# testhat1.net
KiCad netlist of a schematic drawn in Altium Designer
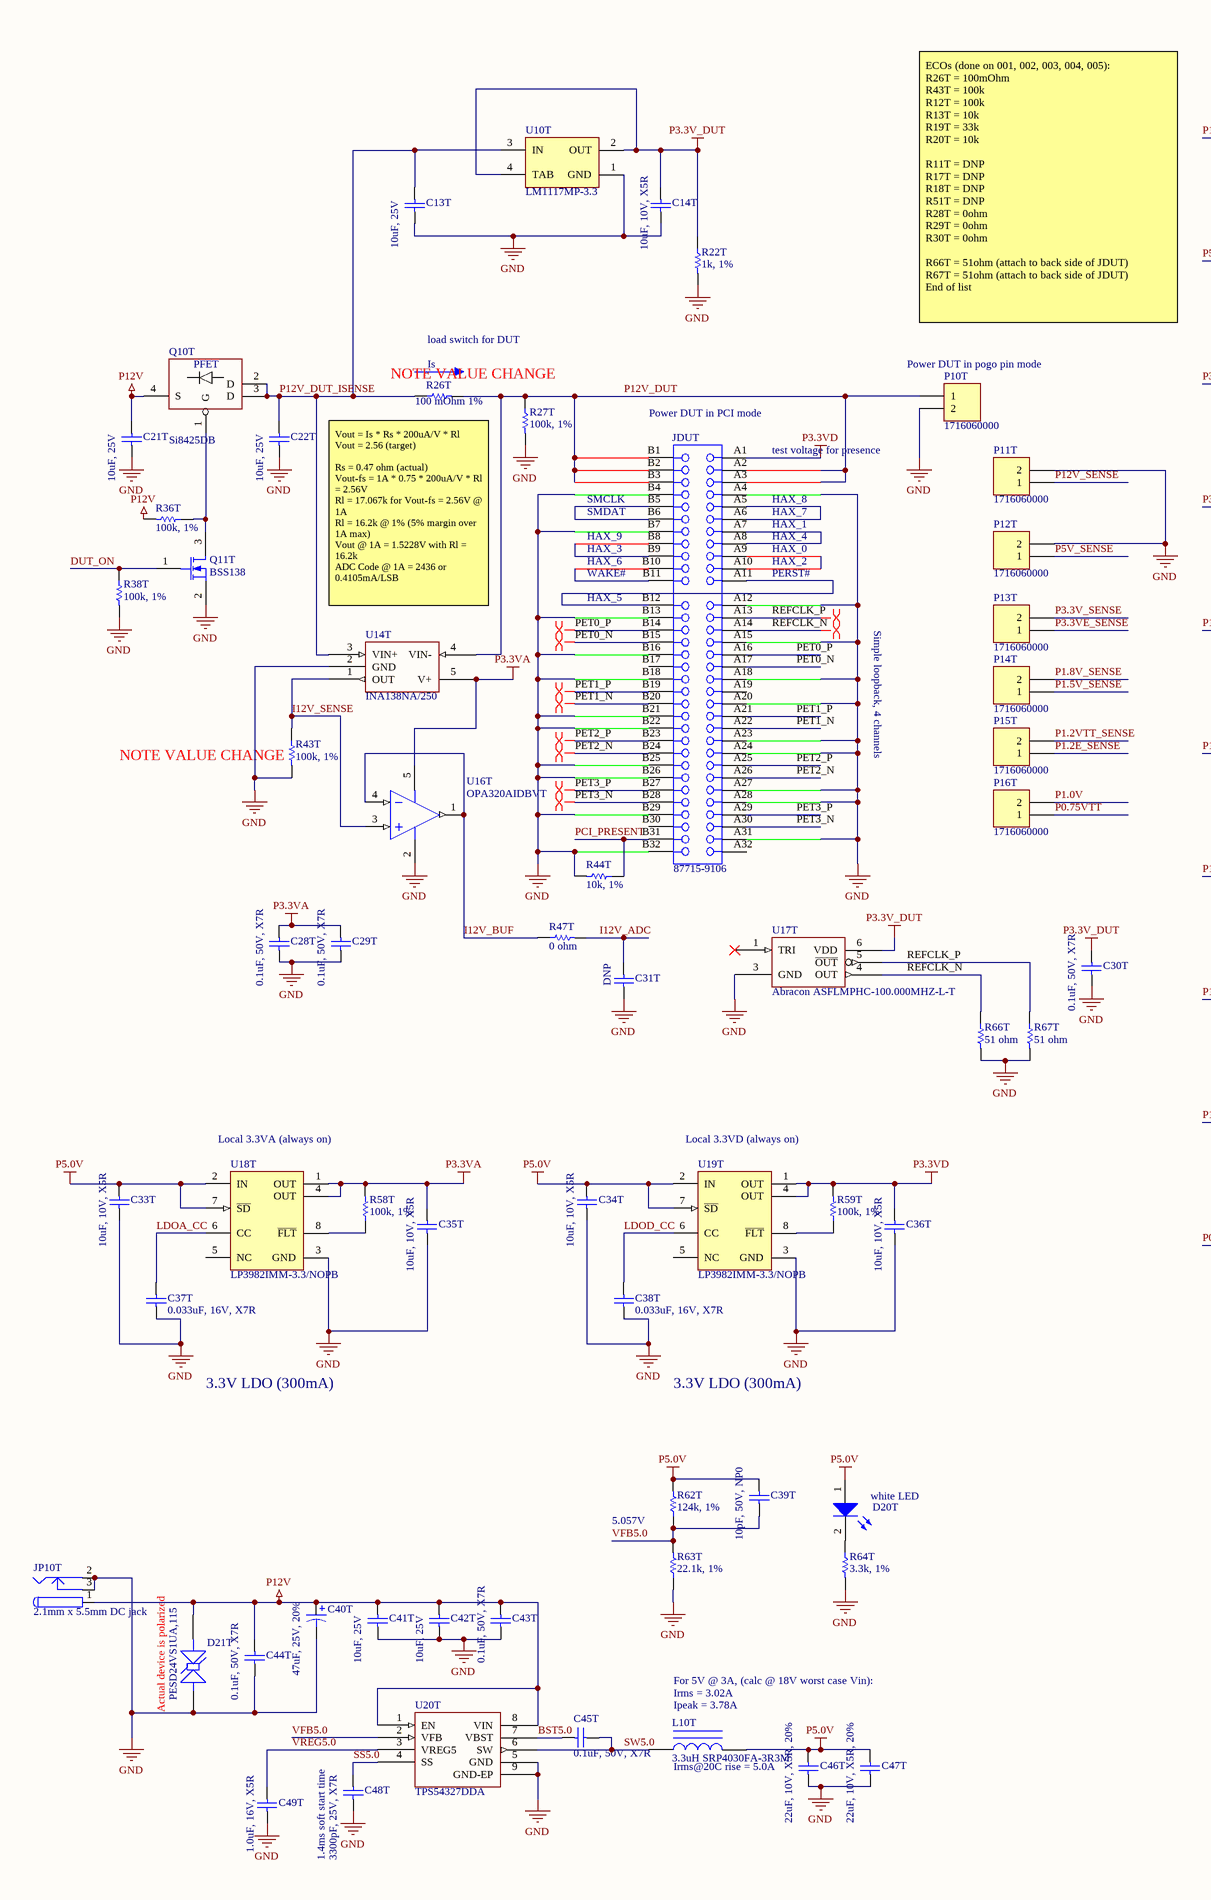
[diagram p0: testhat1.SchDoc, left]
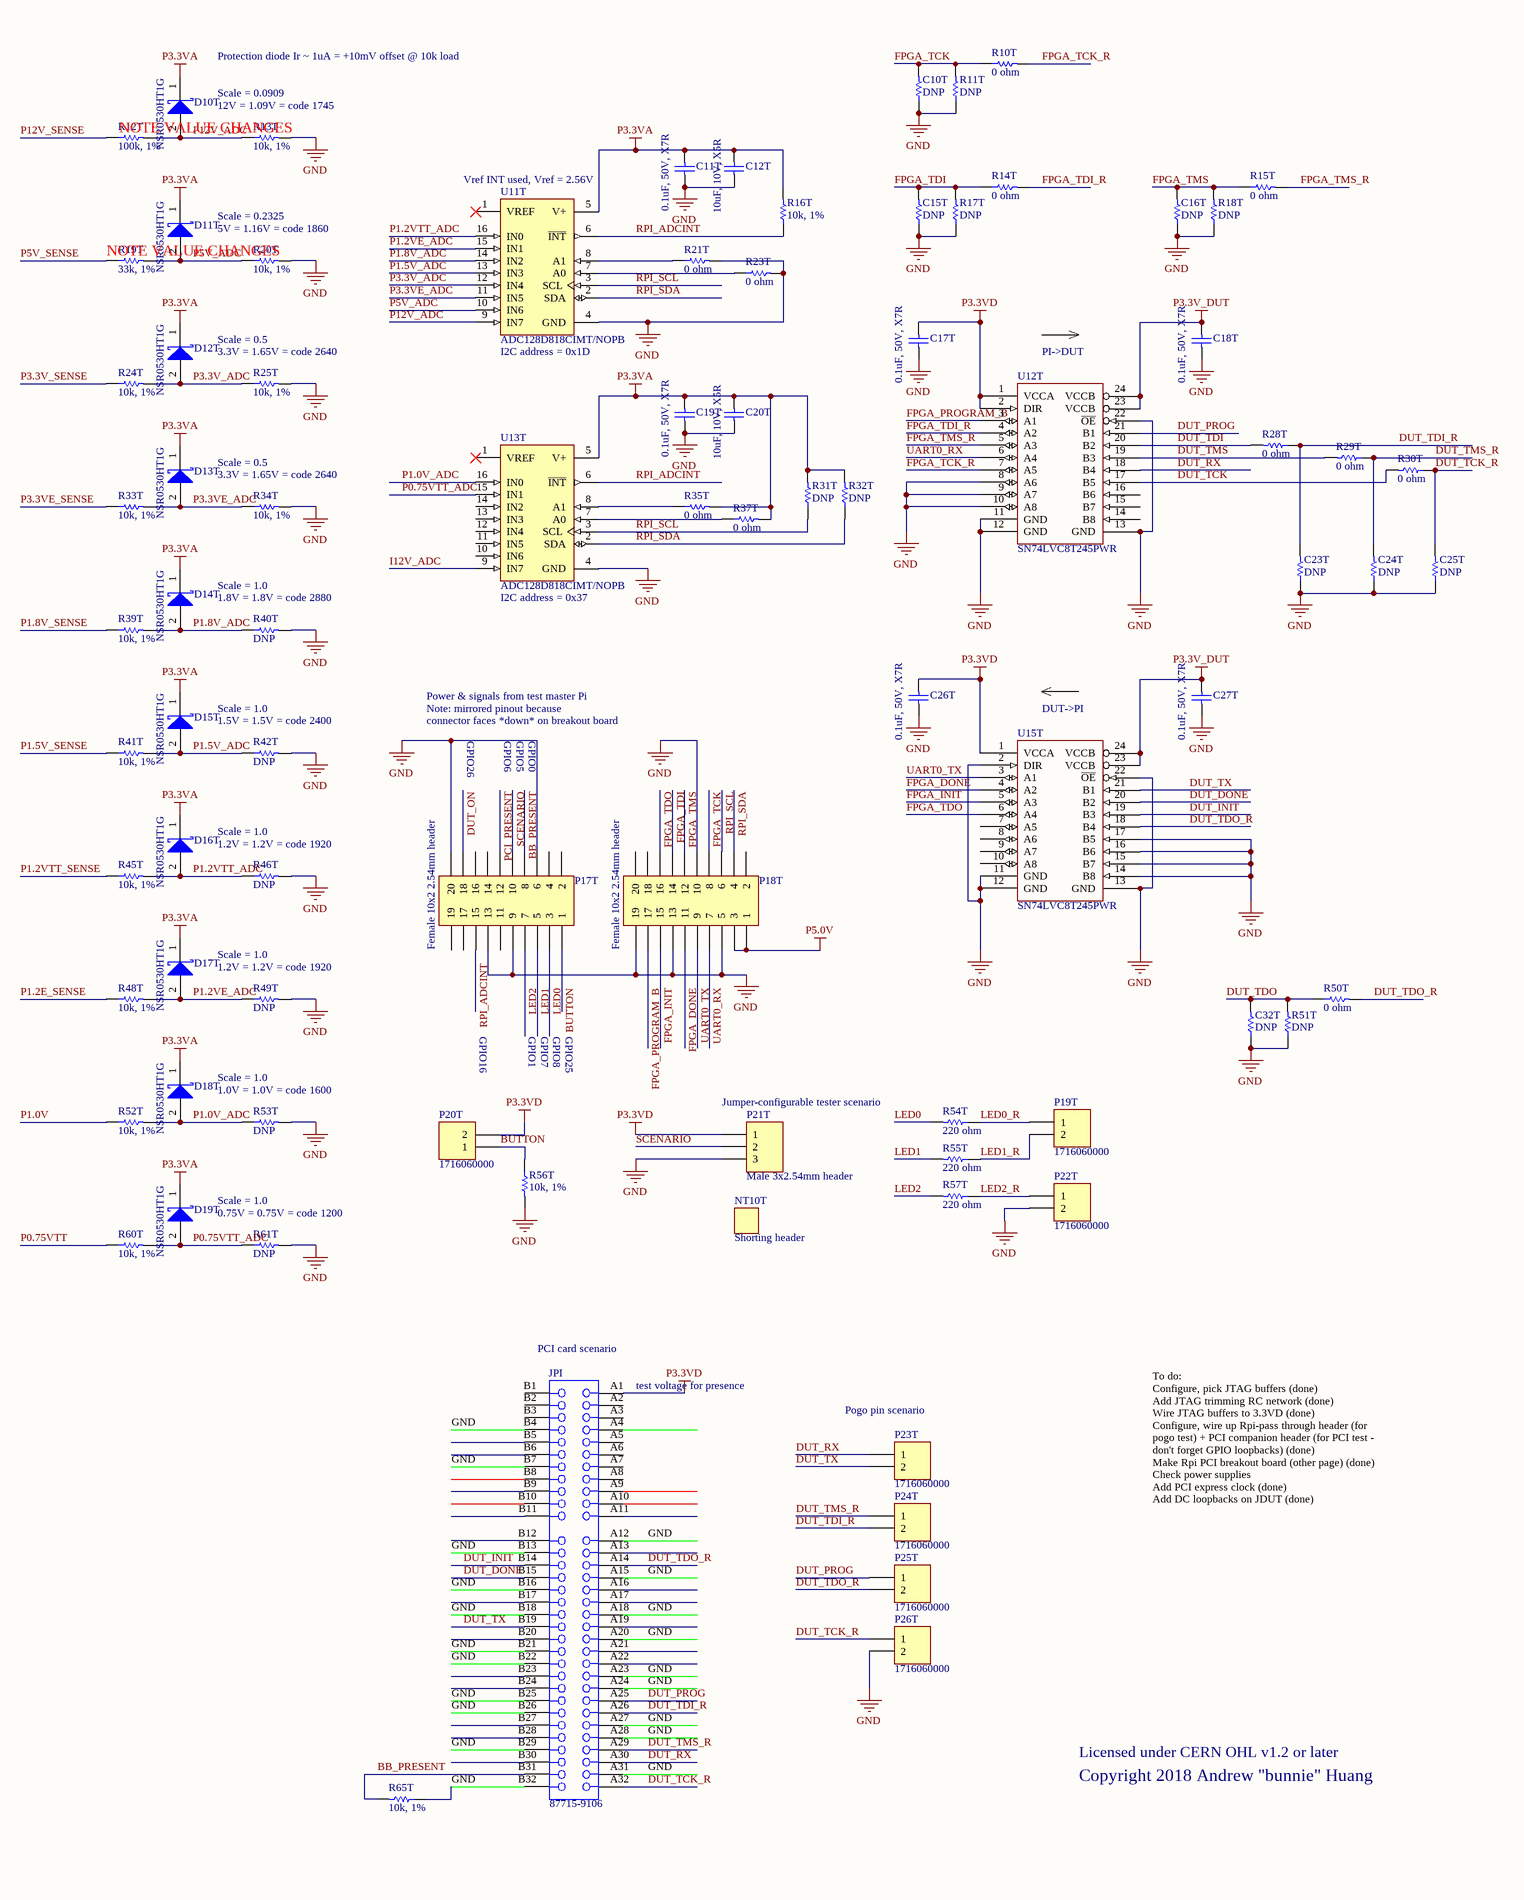
[diagram p1: testhat1.SchDoc, right]

(export (version "E")
  (design (tool "Eeschema 10.0.6"))
  (components
    (comp (ref "C10T")
      (value "DNP")
      (footprint "RESC1608N")
      (description "Resistor")
      (fields (field (name "MPN") "ANY"))
      (libsource (lib "Miscellaneous Devices") (part "Res1"))
    )
    (comp (ref "C11T")
      (value "0.1uF, 50V, X7R")
      (footprint "CAPC2012N")
      (description "Capacitor (Semiconductor SIM Model)")
      (fields (field (name "MPN") "CL21B104KBCNNWC"))
      (libsource (lib "Miscellaneous Devices") (part "Cap Semi"))
    )
    (comp (ref "C12T")
      (value "10uF, 10V, X5R")
      (footprint "CAPC2012N")
      (description "Capacitor (Semiconductor SIM Model)")
      (fields (field (name "MPN") "CL21A106KPCLQNC"))
      (libsource (lib "Miscellaneous Devices") (part "Cap Semi"))
    )
    (comp (ref "C13T")
      (value "10uF, 25V")
      (footprint "CAPC3216N")
      (description "Capacitor (Semiconductor SIM Model)")
      (fields (field (name "MPN") "CL31A106KBHNNNE"))
      (libsource (lib "Miscellaneous Devices") (part "Cap Semi"))
    )
    (comp (ref "C14T")
      (value "10uF, 10V, X5R")
      (footprint "CAPC2012N")
      (description "Capacitor (Semiconductor SIM Model)")
      (fields (field (name "MPN") "CL21A106KPCLQNC"))
      (libsource (lib "Miscellaneous Devices") (part "Cap Semi"))
    )
    (comp (ref "C15T")
      (value "DNP")
      (footprint "RESC1608N")
      (description "Resistor")
      (fields (field (name "MPN") "ANY"))
      (libsource (lib "Miscellaneous Devices") (part "Res1"))
    )
    (comp (ref "C16T")
      (value "DNP")
      (footprint "RESC1608N")
      (description "Resistor")
      (fields (field (name "MPN") "ANY"))
      (libsource (lib "Miscellaneous Devices") (part "Res1"))
    )
    (comp (ref "C17T")
      (value "0.1uF, 50V, X7R")
      (footprint "CAPC2012N")
      (description "Capacitor (Semiconductor SIM Model)")
      (fields (field (name "MPN") "CL21B104KBCNNWC"))
      (libsource (lib "Miscellaneous Devices") (part "Cap Semi"))
    )
    (comp (ref "C18T")
      (value "0.1uF, 50V, X7R")
      (footprint "CAPC2012N")
      (description "Capacitor (Semiconductor SIM Model)")
      (fields (field (name "MPN") "CL21B104KBCNNWC"))
      (libsource (lib "Miscellaneous Devices") (part "Cap Semi"))
    )
    (comp (ref "C19T")
      (value "0.1uF, 50V, X7R")
      (footprint "CAPC2012N")
      (description "Capacitor (Semiconductor SIM Model)")
      (fields (field (name "MPN") "CL21B104KBCNNWC"))
      (libsource (lib "Miscellaneous Devices") (part "Cap Semi"))
    )
    (comp (ref "C20T")
      (value "10uF, 10V, X5R")
      (footprint "CAPC2012N")
      (description "Capacitor (Semiconductor SIM Model)")
      (fields (field (name "MPN") "CL21A106KPCLQNC"))
      (libsource (lib "Miscellaneous Devices") (part "Cap Semi"))
    )
    (comp (ref "C21T")
      (value "10uF, 25V")
      (footprint "CAPC3216N")
      (description "Capacitor (Semiconductor SIM Model)")
      (fields (field (name "MPN") "CL31A106KBHNNNE"))
      (libsource (lib "Miscellaneous Devices") (part "Cap Semi"))
    )
    (comp (ref "C22T")
      (value "10uF, 25V")
      (footprint "CAPC3216N")
      (description "Capacitor (Semiconductor SIM Model)")
      (fields (field (name "MPN") "CL31A106KBHNNNE"))
      (libsource (lib "Miscellaneous Devices") (part "Cap Semi"))
    )
    (comp (ref "C23T")
      (value "DNP")
      (footprint "RESC1608N")
      (description "Resistor")
      (fields (field (name "MPN") "ANY"))
      (libsource (lib "Miscellaneous Devices") (part "Res1"))
    )
    (comp (ref "C24T")
      (value "DNP")
      (footprint "RESC1608N")
      (description "Resistor")
      (fields (field (name "MPN") "ANY"))
      (libsource (lib "Miscellaneous Devices") (part "Res1"))
    )
    (comp (ref "C25T")
      (value "DNP")
      (footprint "RESC1608N")
      (description "Resistor")
      (fields (field (name "MPN") "ANY"))
      (libsource (lib "Miscellaneous Devices") (part "Res1"))
    )
    (comp (ref "C26T")
      (value "0.1uF, 50V, X7R")
      (footprint "CAPC2012N")
      (description "Capacitor (Semiconductor SIM Model)")
      (fields (field (name "MPN") "CL21B104KBCNNWC"))
      (libsource (lib "Miscellaneous Devices") (part "Cap Semi"))
    )
    (comp (ref "C27T")
      (value "0.1uF, 50V, X7R")
      (footprint "CAPC2012N")
      (description "Capacitor (Semiconductor SIM Model)")
      (fields (field (name "MPN") "CL21B104KBCNNWC"))
      (libsource (lib "Miscellaneous Devices") (part "Cap Semi"))
    )
    (comp (ref "C28T")
      (value "0.1uF, 50V, X7R")
      (footprint "CAPC2012N")
      (description "Capacitor (Semiconductor SIM Model)")
      (fields (field (name "MPN") "CL21B104KBCNNWC"))
      (libsource (lib "Miscellaneous Devices") (part "Cap Semi"))
    )
    (comp (ref "C29T")
      (value "0.1uF, 50V, X7R")
      (footprint "CAPC2012N")
      (description "Capacitor (Semiconductor SIM Model)")
      (fields (field (name "MPN") "CL21B104KBCNNWC"))
      (libsource (lib "Miscellaneous Devices") (part "Cap Semi"))
    )
    (comp (ref "C30T")
      (value "0.1uF, 50V, X7R")
      (footprint "CAPC2012N")
      (description "Capacitor (Semiconductor SIM Model)")
      (fields (field (name "MPN") "CL21B104KBCNNWC"))
      (libsource (lib "Miscellaneous Devices") (part "Cap Semi"))
    )
    (comp (ref "C31T")
      (value "DNP")
      (footprint "CAPC2012N")
      (description "Capacitor (Semiconductor SIM Model)")
      (libsource (lib "Miscellaneous Devices") (part "Cap Semi"))
    )
    (comp (ref "C32T")
      (value "DNP")
      (footprint "RESC1608N")
      (description "Resistor")
      (fields (field (name "MPN") "ANY"))
      (libsource (lib "Miscellaneous Devices") (part "Res1"))
    )
    (comp (ref "C33T")
      (value "10uF, 10V, X5R")
      (footprint "CAPC2012N")
      (description "Capacitor (Semiconductor SIM Model)")
      (fields (field (name "MPN") "CL21A106KPCLQNC"))
      (libsource (lib "Miscellaneous Devices") (part "Cap Semi"))
    )
    (comp (ref "C34T")
      (value "10uF, 10V, X5R")
      (footprint "CAPC2012N")
      (description "Capacitor (Semiconductor SIM Model)")
      (fields (field (name "MPN") "CL21A106KPCLQNC"))
      (libsource (lib "Miscellaneous Devices") (part "Cap Semi"))
    )
    (comp (ref "C35T")
      (value "10uF, 10V, X5R")
      (footprint "CAPC2012N")
      (description "Capacitor (Semiconductor SIM Model)")
      (fields (field (name "MPN") "CL21A106KPCLQNC"))
      (libsource (lib "Miscellaneous Devices") (part "Cap Semi"))
    )
    (comp (ref "C36T")
      (value "10uF, 10V, X5R")
      (footprint "CAPC2012N")
      (description "Capacitor (Semiconductor SIM Model)")
      (fields (field (name "MPN") "CL21A106KPCLQNC"))
      (libsource (lib "Miscellaneous Devices") (part "Cap Semi"))
    )
    (comp (ref "C37T")
      (value "0.033uF, 16V, X7R")
      (footprint "CAPC1005N")
      (description "Capacitor (Semiconductor SIM Model)")
      (fields (field (name "MPN") "CL05B333KO5NNNC"))
      (libsource (lib "Miscellaneous Devices") (part "Cap Semi"))
    )
    (comp (ref "C38T")
      (value "0.033uF, 16V, X7R")
      (footprint "CAPC1005N")
      (description "Capacitor (Semiconductor SIM Model)")
      (fields (field (name "MPN") "CL05B333KO5NNNC"))
      (libsource (lib "Miscellaneous Devices") (part "Cap Semi"))
    )
    (comp (ref "C39T")
      (value "10pF, 50V, NP0")
      (footprint "CAPC1005N")
      (description "Capacitor (Semiconductor SIM Model)")
      (fields (field (name "MPN") "GCM1555C1H100JA16D"))
      (libsource (lib "Miscellaneous Devices") (part "Cap Semi"))
    )
    (comp (ref "C40T")
      (value "47uF, 25V, 20%")
      (footprint "CAPAE7066X61N")
      (description "Polarized Capacitor (Radial)")
      (fields (field (name "MPN") "UCL1E470MCL1GS"))
      (libsource (lib "Miscellaneous Devices") (part "Cap Pol1"))
    )
    (comp (ref "C41T")
      (value "10uF, 25V")
      (footprint "CAPC3216N")
      (description "Capacitor (Semiconductor SIM Model)")
      (fields (field (name "MPN") "CL31A106KBHNNNE"))
      (libsource (lib "Miscellaneous Devices") (part "Cap Semi"))
    )
    (comp (ref "C42T")
      (value "10uF, 25V")
      (footprint "CAPC3216N")
      (description "Capacitor (Semiconductor SIM Model)")
      (fields (field (name "MPN") "CL31A106KBHNNNE"))
      (libsource (lib "Miscellaneous Devices") (part "Cap Semi"))
    )
    (comp (ref "C43T")
      (value "0.1uF, 50V, X7R")
      (footprint "CAPC2012N")
      (description "Capacitor (Semiconductor SIM Model)")
      (fields (field (name "MPN") "CL21B104KBCNNWC"))
      (libsource (lib "Miscellaneous Devices") (part "Cap Semi"))
    )
    (comp (ref "C44T")
      (value "0.1uF, 50V, X7R")
      (footprint "CAPC2012N")
      (description "Capacitor (Semiconductor SIM Model)")
      (fields (field (name "MPN") "CL21B104KBCNNWC"))
      (libsource (lib "Miscellaneous Devices") (part "Cap Semi"))
    )
    (comp (ref "C45T")
      (value "0.1uF, 50V, X7R")
      (footprint "CAPC2012N")
      (description "Capacitor (Semiconductor SIM Model)")
      (fields (field (name "MPN") "CL21B104KBCNNWC"))
      (libsource (lib "Miscellaneous Devices") (part "Cap Semi"))
    )
    (comp (ref "C46T")
      (value "22uF, 10V, X5R, 20%")
      (footprint "CAPC2012N")
      (description "Capacitor (Semiconductor SIM Model)")
      (fields
        (field (name "MFG") "Murata")
        (field (name "MPN") "GRM21BR61A226ME51L")
        (field (name "PUBLISHER") "Altium Limited")
      )
      (libsource (lib "Miscellaneous Devices") (part "Cap Semi"))
    )
    (comp (ref "C47T")
      (value "22uF, 10V, X5R, 20%")
      (footprint "CAPC2012N")
      (description "Capacitor (Semiconductor SIM Model)")
      (fields
        (field (name "MFG") "Murata")
        (field (name "MPN") "GRM21BR61A226ME51L")
        (field (name "PUBLISHER") "Altium Limited")
      )
      (libsource (lib "Miscellaneous Devices") (part "Cap Semi"))
    )
    (comp (ref "C48T")
      (value "3300pF, 25V, X7R")
      (footprint "CAPC1005N")
      (description "Capacitor (Semiconductor SIM Model)")
      (fields (field (name "MPN") "CL05B332KA5NNNC"))
      (libsource (lib "Miscellaneous Devices") (part "Cap Semi"))
    )
    (comp (ref "C49T")
      (value "1.0uF, 16V, X5R")
      (footprint "CAPC1005N")
      (description "Capacitor (Semiconductor SIM Model)")
      (fields (field (name "MPN") "ANY"))
      (libsource (lib "Miscellaneous Devices") (part "Cap Semi"))
    )
    (comp (ref "D10T")
      (value "NSR0530HT1G")
      (footprint "SOD-323")
      (description "Schottky Diode")
      (fields (field (name "MPN") "NSR0530H-D"))
      (libsource (lib "Miscellaneous Devices") (part "D Schottky"))
    )
    (comp (ref "D11T")
      (value "NSR0530HT1G")
      (footprint "SOD-323")
      (description "Schottky Diode")
      (fields (field (name "MPN") "NSR0530H-D"))
      (libsource (lib "Miscellaneous Devices") (part "D Schottky"))
    )
    (comp (ref "D12T")
      (value "NSR0530HT1G")
      (footprint "SOD-323")
      (description "Schottky Diode")
      (fields (field (name "MPN") "NSR0530H-D"))
      (libsource (lib "Miscellaneous Devices") (part "D Schottky"))
    )
    (comp (ref "D13T")
      (value "NSR0530HT1G")
      (footprint "SOD-323")
      (description "Schottky Diode")
      (fields (field (name "MPN") "NSR0530H-D"))
      (libsource (lib "Miscellaneous Devices") (part "D Schottky"))
    )
    (comp (ref "D14T")
      (value "NSR0530HT1G")
      (footprint "SOD-323")
      (description "Schottky Diode")
      (fields (field (name "MPN") "NSR0530H-D"))
      (libsource (lib "Miscellaneous Devices") (part "D Schottky"))
    )
    (comp (ref "D15T")
      (value "NSR0530HT1G")
      (footprint "SOD-323")
      (description "Schottky Diode")
      (fields (field (name "MPN") "NSR0530H-D"))
      (libsource (lib "Miscellaneous Devices") (part "D Schottky"))
    )
    (comp (ref "D16T")
      (value "NSR0530HT1G")
      (footprint "SOD-323")
      (description "Schottky Diode")
      (fields (field (name "MPN") "NSR0530H-D"))
      (libsource (lib "Miscellaneous Devices") (part "D Schottky"))
    )
    (comp (ref "D17T")
      (value "NSR0530HT1G")
      (footprint "SOD-323")
      (description "Schottky Diode")
      (fields (field (name "MPN") "NSR0530H-D"))
      (libsource (lib "Miscellaneous Devices") (part "D Schottky"))
    )
    (comp (ref "D18T")
      (value "NSR0530HT1G")
      (footprint "SOD-323")
      (description "Schottky Diode")
      (fields (field (name "MPN") "NSR0530H-D"))
      (libsource (lib "Miscellaneous Devices") (part "D Schottky"))
    )
    (comp (ref "D19T")
      (value "NSR0530HT1G")
      (footprint "SOD-323")
      (description "Schottky Diode")
      (fields (field (name "MPN") "NSR0530H-D"))
      (libsource (lib "Miscellaneous Devices") (part "D Schottky"))
    )
    (comp (ref "D20T")
      (value "white LED")
      (footprint "CD2012-0805")
      (description "Typical RED, GREEN, YELLOW, AMBER GaAs LED")
      (fields (field (name "MPN") "CB-2012QWC-P8"))
      (libsource (lib "Miscellaneous Devices") (part "LED2"))
    )
    (comp (ref "D21T")
      (value "PESD24VS1UA,115")
      (footprint "SOD-323")
      (description "Bidirectional zener diode, Vz 17.1V nom")
      (libsource (lib "commonsch") (part "BIDIR_ESD"))
    )
    (comp (ref "JDUT")
      (value "87715-9106")
      (footprint "BTB1-00-2V64")
      (description "Board-to-Board Connector, PTH, Vertical, Pitch 1.00mm, 64-Position")
      (fields (field (name "MPN") "0877159106") (field (name "PUBLISHER") "Altium"))
      (libsource (lib "Altium Shanghai") (part "CMP-0001-00127-1"))
    )
    (comp (ref "JP10T")
      (value "2.1mm x 5.5mm DC jack")
      (footprint "CUI_PJ_002AH_SMT")
      (description "Low Voltage Power Supply Connector")
      (fields (field (name "MPN") "DC-480-2.0A-SMT") (field (name "PUBLISHER") "Altium Limited"))
      (libsource (lib "Miscellaneous Connectors") (part "PWR2.5"))
    )
    (comp (ref "JPI")
      (value "87715-9106")
      (footprint "BTB1-00-2V64")
      (description "Board-to-Board Connector, PTH, Vertical, Pitch 1.00mm, 64-Position")
      (fields (field (name "MPN") "0877159106") (field (name "PUBLISHER") "Altium"))
      (libsource (lib "Altium Shanghai") (part "CMP-0001-00127-1"))
    )
    (comp (ref "L10T")
      (value "3.3uH SRP4030FA-3R3M")
      (footprint "COILCRAFT_XEL4030")
      (description "Magnetic-Core Inductor")
      (fields (field (name "MPN") "XEL4030-332ME_"))
      (libsource (lib "Miscellaneous Devices") (part "Inductor Iron"))
    )
    (comp (ref "NT10T")
      (value "Shorting header")
      (description "Placeholder for non-board BOM items")
      (fields (field (name "MPN") "NPB02SVAN-RC"))
      (libsource (lib "commonsch") (part "NOTE"))
    )
    (comp (ref "P10T")
      (value "1716060000")
      (footprint "weidmuller_1716060000")
      (description "Header, 2-Pin")
      (fields (field (name "PUBLISHER") "Altium Limited"))
      (libsource (lib "") (part "Header 2_1"))
    )
    (comp (ref "P11T")
      (value "1716060000")
      (footprint "weidmuller_1716060000")
      (description "Header, 2-Pin")
      (fields (field (name "PUBLISHER") "Altium Limited"))
      (libsource (lib "Miscellaneous Connectors") (part "Header 2"))
    )
    (comp (ref "P12T")
      (value "1716060000")
      (footprint "weidmuller_1716060000")
      (description "Header, 2-Pin")
      (fields (field (name "PUBLISHER") "Altium Limited"))
      (libsource (lib "Miscellaneous Connectors") (part "Header 2"))
    )
    (comp (ref "P13T")
      (value "1716060000")
      (footprint "weidmuller_1716060000")
      (description "Header, 2-Pin")
      (fields (field (name "PUBLISHER") "Altium Limited"))
      (libsource (lib "Miscellaneous Connectors") (part "Header 2"))
    )
    (comp (ref "P14T")
      (value "1716060000")
      (footprint "weidmuller_1716060000")
      (description "Header, 2-Pin")
      (fields (field (name "PUBLISHER") "Altium Limited"))
      (libsource (lib "Miscellaneous Connectors") (part "Header 2"))
    )
    (comp (ref "P15T")
      (value "1716060000")
      (footprint "weidmuller_1716060000")
      (description "Header, 2-Pin")
      (fields (field (name "PUBLISHER") "Altium Limited"))
      (libsource (lib "Miscellaneous Connectors") (part "Header 2"))
    )
    (comp (ref "P16T")
      (value "1716060000")
      (footprint "weidmuller_1716060000")
      (description "Header, 2-Pin")
      (fields (field (name "PUBLISHER") "Altium Limited"))
      (libsource (lib "Miscellaneous Connectors") (part "Header 2"))
    )
    (comp (ref "P17T")
      (value "Female 10x2 2.54mm header")
      (footprint "HDR2X10")
      (description "Header, 10-Pin, Dual row")
      (fields (field (name "MPN") "F201-SGP-D048-20-P4") (field (name "PUBLISHER") "Altium Limited"))
      (libsource (lib "Miscellaneous Connectors") (part "Header 10X2"))
    )
    (comp (ref "P18T")
      (value "Female 10x2 2.54mm header")
      (footprint "HDR2X10")
      (description "Header, 10-Pin, Dual row")
      (fields (field (name "MPN") "F201-SGP-D048-20-P4") (field (name "PUBLISHER") "Altium Limited"))
      (libsource (lib "Miscellaneous Connectors") (part "Header 10X2"))
    )
    (comp (ref "P19T")
      (value "1716060000")
      (footprint "weidmuller_1716060000")
      (description "Header, 2-Pin")
      (fields (field (name "PUBLISHER") "Altium Limited"))
      (libsource (lib "") (part "Header 2_1"))
    )
    (comp (ref "P20T")
      (value "1716060000")
      (footprint "weidmuller_1716060000")
      (description "Header, 2-Pin")
      (fields (field (name "PUBLISHER") "Altium Limited"))
      (libsource (lib "Miscellaneous Connectors") (part "Header 2"))
    )
    (comp (ref "P21T")
      (value "Male 3x2.54mm header")
      (footprint "HDR1X3")
      (description "Header, 3-Pin")
      (fields (field (name "MPN") "CP25411-03G-S116-X") (field (name "PUBLISHER") "Altium Limited"))
      (libsource (lib "Miscellaneous Connectors") (part "Header 3"))
    )
    (comp (ref "P22T")
      (value "1716060000")
      (footprint "weidmuller_1716060000")
      (description "Header, 2-Pin")
      (fields (field (name "PUBLISHER") "Altium Limited"))
      (libsource (lib "") (part "Header 2_1"))
    )
    (comp (ref "P23T")
      (value "1716060000")
      (footprint "weidmuller_1716060000")
      (description "Header, 2-Pin")
      (fields (field (name "PUBLISHER") "Altium Limited"))
      (libsource (lib "") (part "Header 2_1"))
    )
    (comp (ref "P24T")
      (value "1716060000")
      (footprint "weidmuller_1716060000")
      (description "Header, 2-Pin")
      (fields (field (name "PUBLISHER") "Altium Limited"))
      (libsource (lib "") (part "Header 2_1"))
    )
    (comp (ref "P25T")
      (value "1716060000")
      (footprint "weidmuller_1716060000")
      (description "Header, 2-Pin")
      (fields (field (name "PUBLISHER") "Altium Limited"))
      (libsource (lib "") (part "Header 2_1"))
    )
    (comp (ref "P26T")
      (value "1716060000")
      (footprint "weidmuller_1716060000")
      (description "Header, 2-Pin")
      (fields (field (name "PUBLISHER") "Altium Limited"))
      (libsource (lib "") (part "Header 2_1"))
    )
    (comp (ref "Q10T")
      (value "Si8425DB")
      (footprint "VISHAY_MICRO_FOOT_4_BUMP")
      (description "P-channel 20V 6.2A 27mOhm @ -2.5V")
      (fields (field (name "MPN") "Si8425DB-T1-E1"))
      (libsource (lib "temp-to-merge") (part "Si8425DB"))
    )
    (comp (ref "Q11T")
      (value "BSS138")
      (footprint "SOT23-3N")
      (description "N-Channel MOSFET")
      (fields (field (name "MPN") "BSS138LT1G") (field (name "PUBLISHER") "Altium Limited"))
      (libsource (lib "Miscellaneous Devices") (part "MOSFET-N"))
    )
    (comp (ref "R10T")
      (value "0 ohm")
      (footprint "RESC1608N")
      (description "Resistor")
      (fields (field (name "MPN") "ANY"))
      (libsource (lib "Miscellaneous Devices") (part "Res1"))
    )
    (comp (ref "R11T")
      (value "DNP")
      (footprint "RESC1608N")
      (description "Resistor")
      (fields (field (name "MPN") "ANY"))
      (libsource (lib "Miscellaneous Devices") (part "Res1"))
    )
    (comp (ref "R12T")
      (value "100k, 1%")
      (footprint "RESC1005N")
      (description "Resistor")
      (fields (field (name "MPN") "ANY"))
      (libsource (lib "Miscellaneous Devices") (part "Res1"))
    )
    (comp (ref "R13T")
      (value "10k, 1%")
      (footprint "RESC1005N")
      (description "Resistor")
      (fields (field (name "MPN") "ANY"))
      (libsource (lib "Miscellaneous Devices") (part "Res1"))
    )
    (comp (ref "R14T")
      (value "0 ohm")
      (footprint "RESC1608N")
      (description "Resistor")
      (fields (field (name "MPN") "ANY"))
      (libsource (lib "Miscellaneous Devices") (part "Res1"))
    )
    (comp (ref "R15T")
      (value "0 ohm")
      (footprint "RESC1608N")
      (description "Resistor")
      (fields (field (name "MPN") "ANY"))
      (libsource (lib "Miscellaneous Devices") (part "Res1"))
    )
    (comp (ref "R16T")
      (value "10k, 1%")
      (footprint "RESC1005N")
      (description "Resistor")
      (fields (field (name "MPN") "ANY"))
      (libsource (lib "Miscellaneous Devices") (part "Res1"))
    )
    (comp (ref "R17T")
      (value "DNP")
      (footprint "RESC1608N")
      (description "Resistor")
      (fields (field (name "MPN") "ANY"))
      (libsource (lib "Miscellaneous Devices") (part "Res1"))
    )
    (comp (ref "R18T")
      (value "DNP")
      (footprint "RESC1608N")
      (description "Resistor")
      (fields (field (name "MPN") "ANY"))
      (libsource (lib "Miscellaneous Devices") (part "Res1"))
    )
    (comp (ref "R19T")
      (value "33k, 1%")
      (footprint "RESC1005N")
      (description "Resistor")
      (fields (field (name "MPN") "ANY"))
      (libsource (lib "Miscellaneous Devices") (part "Res1"))
    )
    (comp (ref "R20T")
      (value "10k, 1%")
      (footprint "RESC1005N")
      (description "Resistor")
      (fields (field (name "MPN") "ANY"))
      (libsource (lib "Miscellaneous Devices") (part "Res1"))
    )
    (comp (ref "R21T")
      (value "0 ohm")
      (footprint "RESC1608N")
      (description "Resistor")
      (fields (field (name "MPN") "ANY"))
      (libsource (lib "Miscellaneous Devices") (part "Res1"))
    )
    (comp (ref "R22T")
      (value "1k, 1%")
      (footprint "RESC1608N")
      (description "Resistor")
      (fields (field (name "MPN") "ANY") (field (name "PUBLISHER") "Altium Limited"))
      (libsource (lib "Miscellaneous Devices") (part "Res1"))
    )
    (comp (ref "R23T")
      (value "0 ohm")
      (footprint "RESC1608N")
      (description "Resistor")
      (fields (field (name "MPN") "ANY"))
      (libsource (lib "Miscellaneous Devices") (part "Res1"))
    )
    (comp (ref "R24T")
      (value "10k, 1%")
      (footprint "RESC1005N")
      (description "Resistor")
      (fields (field (name "MPN") "ANY"))
      (libsource (lib "Miscellaneous Devices") (part "Res1"))
    )
    (comp (ref "R25T")
      (value "10k, 1%")
      (footprint "RESC1005N")
      (description "Resistor")
      (fields (field (name "MPN") "ANY"))
      (libsource (lib "Miscellaneous Devices") (part "Res1"))
    )
    (comp (ref "R26T")
      (value "100 mOhm 1%")
      (footprint "RESC3216N")
      (description "Resistor")
      (fields (field (name "MPN") "ECO"))
      (libsource (lib "Miscellaneous Devices") (part "Res1"))
    )
    (comp (ref "R27T")
      (value "100k, 1%")
      (footprint "RESC1005N")
      (description "Resistor")
      (fields (field (name "MPN") "ANY"))
      (libsource (lib "Miscellaneous Devices") (part "Res1"))
    )
    (comp (ref "R28T")
      (value "0 ohm")
      (footprint "RESC1608N")
      (description "Resistor")
      (fields (field (name "MPN") "ANY"))
      (libsource (lib "Miscellaneous Devices") (part "Res1"))
    )
    (comp (ref "R29T")
      (value "0 ohm")
      (footprint "RESC1608N")
      (description "Resistor")
      (fields (field (name "MPN") "ANY"))
      (libsource (lib "Miscellaneous Devices") (part "Res1"))
    )
    (comp (ref "R30T")
      (value "0 ohm")
      (footprint "RESC1608N")
      (description "Resistor")
      (fields (field (name "MPN") "ANY"))
      (libsource (lib "Miscellaneous Devices") (part "Res1"))
    )
    (comp (ref "R31T")
      (value "DNP")
      (footprint "RESC1005N")
      (description "Resistor")
      (fields (field (name "MPN") "ANY"))
      (libsource (lib "Miscellaneous Devices") (part "Res1"))
    )
    (comp (ref "R32T")
      (value "DNP")
      (footprint "RESC1005N")
      (description "Resistor")
      (fields (field (name "MPN") "ANY"))
      (libsource (lib "Miscellaneous Devices") (part "Res1"))
    )
    (comp (ref "R33T")
      (value "10k, 1%")
      (footprint "RESC1005N")
      (description "Resistor")
      (fields (field (name "MPN") "ANY"))
      (libsource (lib "Miscellaneous Devices") (part "Res1"))
    )
    (comp (ref "R34T")
      (value "10k, 1%")
      (footprint "RESC1005N")
      (description "Resistor")
      (fields (field (name "MPN") "ANY"))
      (libsource (lib "Miscellaneous Devices") (part "Res1"))
    )
    (comp (ref "R35T")
      (value "0 ohm")
      (footprint "RESC1608N")
      (description "Resistor")
      (fields (field (name "MPN") "ANY"))
      (libsource (lib "Miscellaneous Devices") (part "Res1"))
    )
    (comp (ref "R36T")
      (value "100k, 1%")
      (footprint "RESC1005N")
      (description "Resistor")
      (fields (field (name "MPN") "ANY"))
      (libsource (lib "Miscellaneous Devices") (part "Res1"))
    )
    (comp (ref "R37T")
      (value "0 ohm")
      (footprint "RESC1608N")
      (description "Resistor")
      (fields (field (name "MPN") "ANY"))
      (libsource (lib "Miscellaneous Devices") (part "Res1"))
    )
    (comp (ref "R38T")
      (value "100k, 1%")
      (footprint "RESC1005N")
      (description "Resistor")
      (fields (field (name "MPN") "ANY"))
      (libsource (lib "Miscellaneous Devices") (part "Res1"))
    )
    (comp (ref "R39T")
      (value "10k, 1%")
      (footprint "RESC1005N")
      (description "Resistor")
      (fields (field (name "MPN") "ANY"))
      (libsource (lib "Miscellaneous Devices") (part "Res1"))
    )
    (comp (ref "R40T")
      (value "DNP")
      (footprint "RESC1005N")
      (description "Resistor")
      (fields (field (name "MPN") "ANY"))
      (libsource (lib "Miscellaneous Devices") (part "Res1"))
    )
    (comp (ref "R41T")
      (value "10k, 1%")
      (footprint "RESC1005N")
      (description "Resistor")
      (fields (field (name "MPN") "ANY"))
      (libsource (lib "Miscellaneous Devices") (part "Res1"))
    )
    (comp (ref "R42T")
      (value "DNP")
      (footprint "RESC1005N")
      (description "Resistor")
      (fields (field (name "MPN") "ANY"))
      (libsource (lib "Miscellaneous Devices") (part "Res1"))
    )
    (comp (ref "R43T")
      (value "100k, 1%")
      (footprint "RESC1005N")
      (description "Resistor")
      (fields (field (name "MPN") "ANY"))
      (libsource (lib "Miscellaneous Devices") (part "Res1"))
    )
    (comp (ref "R44T")
      (value "10k, 1%")
      (footprint "RESC1005N")
      (description "Resistor")
      (fields (field (name "MPN") "ANY"))
      (libsource (lib "Miscellaneous Devices") (part "Res1"))
    )
    (comp (ref "R45T")
      (value "10k, 1%")
      (footprint "RESC1005N")
      (description "Resistor")
      (fields (field (name "MPN") "ANY"))
      (libsource (lib "Miscellaneous Devices") (part "Res1"))
    )
    (comp (ref "R46T")
      (value "DNP")
      (footprint "RESC1005N")
      (description "Resistor")
      (fields (field (name "MPN") "ANY"))
      (libsource (lib "Miscellaneous Devices") (part "Res1"))
    )
    (comp (ref "R47T")
      (value "0 ohm")
      (footprint "RESC1608N")
      (description "Resistor")
      (fields (field (name "MPN") "ANY"))
      (libsource (lib "Miscellaneous Devices") (part "Res1"))
    )
    (comp (ref "R48T")
      (value "10k, 1%")
      (footprint "RESC1005N")
      (description "Resistor")
      (fields (field (name "MPN") "ANY"))
      (libsource (lib "Miscellaneous Devices") (part "Res1"))
    )
    (comp (ref "R49T")
      (value "DNP")
      (footprint "RESC1005N")
      (description "Resistor")
      (fields (field (name "MPN") "ANY"))
      (libsource (lib "Miscellaneous Devices") (part "Res1"))
    )
    (comp (ref "R50T")
      (value "0 ohm")
      (footprint "RESC1608N")
      (description "Resistor")
      (fields (field (name "MPN") "ANY"))
      (libsource (lib "Miscellaneous Devices") (part "Res1"))
    )
    (comp (ref "R51T")
      (value "DNP")
      (footprint "RESC1608N")
      (description "Resistor")
      (fields (field (name "MPN") "ANY"))
      (libsource (lib "Miscellaneous Devices") (part "Res1"))
    )
    (comp (ref "R52T")
      (value "10k, 1%")
      (footprint "RESC1005N")
      (description "Resistor")
      (fields (field (name "MPN") "ANY"))
      (libsource (lib "Miscellaneous Devices") (part "Res1"))
    )
    (comp (ref "R53T")
      (value "DNP")
      (footprint "RESC1005N")
      (description "Resistor")
      (fields (field (name "MPN") "ANY"))
      (libsource (lib "Miscellaneous Devices") (part "Res1"))
    )
    (comp (ref "R54T")
      (value "220 ohm")
      (footprint "RESC1608N")
      (description "Resistor")
      (fields (field (name "MPN") "ANY"))
      (libsource (lib "Miscellaneous Devices") (part "Res1"))
    )
    (comp (ref "R55T")
      (value "220 ohm")
      (footprint "RESC1608N")
      (description "Resistor")
      (fields (field (name "MPN") "ANY"))
      (libsource (lib "Miscellaneous Devices") (part "Res1"))
    )
    (comp (ref "R56T")
      (value "10k, 1%")
      (footprint "RESC1005N")
      (description "Resistor")
      (fields (field (name "MPN") "ANY"))
      (libsource (lib "Miscellaneous Devices") (part "Res1"))
    )
    (comp (ref "R57T")
      (value "220 ohm")
      (footprint "RESC1608N")
      (description "Resistor")
      (fields (field (name "MPN") "ANY"))
      (libsource (lib "Miscellaneous Devices") (part "Res1"))
    )
    (comp (ref "R58T")
      (value "100k, 1%")
      (footprint "RESC1005N")
      (description "Resistor")
      (fields (field (name "MPN") "ANY"))
      (libsource (lib "Miscellaneous Devices") (part "Res1"))
    )
    (comp (ref "R59T")
      (value "100k, 1%")
      (footprint "RESC1005N")
      (description "Resistor")
      (fields (field (name "MPN") "ANY"))
      (libsource (lib "Miscellaneous Devices") (part "Res1"))
    )
    (comp (ref "R60T")
      (value "10k, 1%")
      (footprint "RESC1005N")
      (description "Resistor")
      (fields (field (name "MPN") "ANY"))
      (libsource (lib "Miscellaneous Devices") (part "Res1"))
    )
    (comp (ref "R61T")
      (value "DNP")
      (footprint "RESC1005N")
      (description "Resistor")
      (fields (field (name "MPN") "ANY"))
      (libsource (lib "Miscellaneous Devices") (part "Res1"))
    )
    (comp (ref "R62T")
      (value "124k, 1%")
      (footprint "RESC1005N")
      (description "Resistor")
      (fields (field (name "MPN") "ANY"))
      (libsource (lib "Miscellaneous Devices") (part "Res1"))
    )
    (comp (ref "R63T")
      (value "22.1k, 1%")
      (footprint "RESC1005N")
      (description "Resistor")
      (fields (field (name "MPN") "ANY"))
      (libsource (lib "Miscellaneous Devices") (part "Res1"))
    )
    (comp (ref "R64T")
      (value "3.3k, 1%")
      (footprint "RESC1005N")
      (description "Resistor")
      (fields (field (name "MPN") "RS02U332FT") (field (name "PUBLISHER") "Altium Limited"))
      (libsource (lib "Miscellaneous Devices") (part "Res1"))
    )
    (comp (ref "R65T")
      (value "10k, 1%")
      (footprint "RESC1005N")
      (description "Resistor")
      (fields (field (name "MPN") "ANY"))
      (libsource (lib "Miscellaneous Devices") (part "Res1"))
    )
    (comp (ref "R66T")
      (value "51 ohm")
      (footprint "RESC1608N")
      (description "Resistor")
      (fields (field (name "MPN") "ANY"))
      (libsource (lib "Miscellaneous Devices") (part "Res1"))
    )
    (comp (ref "R67T")
      (value "51 ohm")
      (footprint "RESC1608N")
      (description "Resistor")
      (fields (field (name "MPN") "ANY"))
      (libsource (lib "Miscellaneous Devices") (part "Res1"))
    )
    (comp (ref "U10T")
      (value "LM1117MP-3.3")
      (footprint "MP04A_N")
      (description "800mA Low-Dropout Linear Regulator, 4-pin SOT-223")
      (fields (field (name "MANUFACTURER") "National Semiconductor"))
      (libsource (lib "National Semiconductor LDO") (part "LM1117MP-3.3"))
    )
    (comp (ref "U11T")
      (value "ADC128D818CIMT/NOPB")
      (footprint "MTC16_N")
      (fields (field (name "MANUFACTURER") "National Semiconductor"))
      (libsource (lib "National Semiconductor ADC") (part "ADC128D818CIMT/NOPB"))
    )
    (comp (ref "U12T")
      (value "SN74LVC8T245PWR")
      (footprint "TSOP65P640-24AN")
      (description "8-bit dual-supply transceiver")
      (fields (field (name "MPN") "SN74LVC8T245PW"))
      (libsource (lib "commonsch") (part "SN74LVC8T245PWR"))
    )
    (comp (ref "U13T")
      (value "ADC128D818CIMT/NOPB")
      (footprint "MTC16_N")
      (fields (field (name "MANUFACTURER") "National Semiconductor"))
      (libsource (lib "National Semiconductor ADC") (part "ADC128D818CIMT/NOPB"))
    )
    (comp (ref "U14T")
      (value "INA138NA/250")
      (footprint "SOT23-5AN")
      (description "High-side measurement current shunt monitor")
      (libsource (lib "commonsch-new") (part "INA138NA/250"))
    )
    (comp (ref "U15T")
      (value "SN74LVC8T245PWR")
      (footprint "TSOP65P640-24AN")
      (description "8-bit dual-supply transceiver")
      (libsource (lib "commonsch") (part "SN74LVC8T245PWR"))
    )
    (comp (ref "U16T")
      (value "OPA320AIDBVT")
      (footprint "TI-DBV5_N")
      (fields (field (name "MANUFACTURER") "Texas Instruments"))
      (libsource (lib "TI Amplifiers and Linear Operational Amplifier Precision Amplifier Part One") (part "OPA320AIDBVT"))
    )
    (comp (ref "U17T")
      (value "Abracon ASFLMPHC-100.000MHZ-L-T")
      (footprint "ABRACON_ASFLMP_HC")
      (description "Abracon Plastic Package Ultra Miniature Pure Silicon Clock Oscillator")
      (fields (field (name "MPN") "ASFLMPHC-100.000MHZ-L-T"))
      (libsource (lib "commonsch-new") (part "HCSL-OSC"))
    )
    (comp (ref "U18T")
      (value "LP3982IMM-3.3/NOPB")
      (footprint "MUA08A_N")
      (description "Micropower, Ultra Low-Dropout, Low-Noise, 300mA CMOS Regulator, 8-pin Mini SOIC, Pb-Free")
      (fields (field (name "MANUFACTURER") "National Semiconductor"))
      (libsource (lib "National Semiconductor LDO") (part "LP3982IMM-3.3/NOPB"))
    )
    (comp (ref "U19T")
      (value "LP3982IMM-3.3/NOPB")
      (footprint "MUA08A_N")
      (description "Micropower, Ultra Low-Dropout, Low-Noise, 300mA CMOS Regulator, 8-pin Mini SOIC, Pb-Free")
      (fields (field (name "MANUFACTURER") "National Semiconductor"))
      (libsource (lib "National Semiconductor LDO") (part "LP3982IMM-3.3/NOPB"))
    )
    (comp (ref "U20T")
      (value "TPS54327DDA")
      (footprint "SOIC127P600-8DN")
      (description "3-A Output Single Synchronous Step-Down Buck with Integrated FET")
      (fields (field (name "MPN") "TPS54327DDA(R)"))
      (libsource (lib "commonsch-new") (part "TPS54327DDA"))
    )
  )
  (nets
    (net (code "1") (name "/BB_PRESENT") (class "Default")
      (node (ref "JPI") (pin "B31") (pinfunction "B31_B31") (pintype "passive"))
      (node (ref "P17T") (pin "8") (pinfunction "8_8") (pintype "passive"))
      (node (ref "R65T") (pin "2") (pinfunction "2_2") (pintype "passive"))
    )
    (net (code "2") (name "/BST5.0") (class "Default")
      (node (ref "C45T") (pin "2") (pinfunction "2_2") (pintype "passive"))
      (node (ref "U20T") (pin "7") (pinfunction "VBST_7") (pintype "passive"))
    )
    (net (code "3") (name "/BUTTON") (class "Default")
      (node (ref "P17T") (pin "1") (pinfunction "1_1") (pintype "passive"))
      (node (ref "P20T") (pin "1") (pinfunction "1_1") (pintype "passive"))
      (node (ref "R56T") (pin "1") (pinfunction "1_1") (pintype "passive"))
    )
    (net (code "4") (name "/DUT_DONE") (class "Default")
      (node (ref "JPI") (pin "B15") (pinfunction "B15_B15") (pintype "passive"))
      (node (ref "U15T") (pin "20") (pinfunction "B2_20") (pintype "input"))
    )
    (net (code "5") (name "/DUT_INIT") (class "Default")
      (node (ref "JPI") (pin "B14") (pinfunction "B14_B14") (pintype "passive"))
      (node (ref "U15T") (pin "19") (pinfunction "B3_19") (pintype "input"))
    )
    (net (code "6") (name "/DUT_ON") (class "Default")
      (node (ref "P17T") (pin "18") (pinfunction "18_18") (pintype "passive"))
      (node (ref "Q11T") (pin "1") (pinfunction "G_1") (pintype "passive"))
      (node (ref "R38T") (pin "1") (pinfunction "1_1") (pintype "passive"))
    )
    (net (code "7") (name "/DUT_PROG") (class "Default")
      (node (ref "JPI") (pin "A25") (pinfunction "A25_A25") (pintype "passive"))
      (node (ref "P25T") (pin "1") (pinfunction "1_1") (pintype "passive"))
      (node (ref "U12T") (pin "21") (pinfunction "B1_21") (pintype "input"))
    )
    (net (code "8") (name "/DUT_RX") (class "Default")
      (node (ref "JPI") (pin "A30") (pinfunction "A30_A30") (pintype "passive"))
      (node (ref "P23T") (pin "1") (pinfunction "1_1") (pintype "passive"))
      (node (ref "U12T") (pin "18") (pinfunction "B4_18") (pintype "input"))
    )
    (net (code "9") (name "/DUT_TCK") (class "Default")
      (node (ref "R30T") (pin "2") (pinfunction "2_2") (pintype "passive"))
      (node (ref "U12T") (pin "17") (pinfunction "B5_17") (pintype "input"))
    )
    (net (code "10") (name "/DUT_TCK_R") (class "Default")
      (node (ref "C25T") (pin "2") (pinfunction "2_2") (pintype "passive"))
      (node (ref "JPI") (pin "A32") (pinfunction "A32_A32") (pintype "passive"))
      (node (ref "P26T") (pin "1") (pinfunction "1_1") (pintype "passive"))
      (node (ref "R30T") (pin "1") (pinfunction "1_1") (pintype "passive"))
    )
    (net (code "11") (name "/DUT_TDI") (class "Default")
      (node (ref "R28T") (pin "2") (pinfunction "2_2") (pintype "passive"))
      (node (ref "U12T") (pin "20") (pinfunction "B2_20") (pintype "input"))
    )
    (net (code "12") (name "/DUT_TDI_R") (class "Default")
      (node (ref "C23T") (pin "2") (pinfunction "2_2") (pintype "passive"))
      (node (ref "JPI") (pin "A26") (pinfunction "A26_A26") (pintype "passive"))
      (node (ref "P24T") (pin "2") (pinfunction "2_2") (pintype "passive"))
      (node (ref "R28T") (pin "1") (pinfunction "1_1") (pintype "passive"))
    )
    (net (code "13") (name "/DUT_TDO") (class "Default")
      (node (ref "C32T") (pin "2") (pinfunction "2_2") (pintype "passive"))
      (node (ref "R50T") (pin "1") (pinfunction "1_1") (pintype "passive"))
      (node (ref "R51T") (pin "2") (pinfunction "2_2") (pintype "passive"))
    )
    (net (code "14") (name "/DUT_TDO_R") (class "Default")
      (node (ref "JPI") (pin "A14") (pinfunction "A14_A14") (pintype "passive"))
      (node (ref "P25T") (pin "2") (pinfunction "2_2") (pintype "passive"))
      (node (ref "R50T") (pin "2") (pinfunction "2_2") (pintype "passive"))
      (node (ref "U15T") (pin "18") (pinfunction "B4_18") (pintype "input"))
    )
    (net (code "15") (name "/DUT_TMS") (class "Default")
      (node (ref "R29T") (pin "2") (pinfunction "2_2") (pintype "passive"))
      (node (ref "U12T") (pin "19") (pinfunction "B3_19") (pintype "input"))
    )
    (net (code "16") (name "/DUT_TMS_R") (class "Default")
      (node (ref "C24T") (pin "2") (pinfunction "2_2") (pintype "passive"))
      (node (ref "JPI") (pin "A29") (pinfunction "A29_A29") (pintype "passive"))
      (node (ref "P24T") (pin "1") (pinfunction "1_1") (pintype "passive"))
      (node (ref "R29T") (pin "1") (pinfunction "1_1") (pintype "passive"))
    )
    (net (code "17") (name "/DUT_TX") (class "Default")
      (node (ref "JPI") (pin "B19") (pinfunction "B19_B19") (pintype "passive"))
      (node (ref "P23T") (pin "2") (pinfunction "2_2") (pintype "passive"))
      (node (ref "U15T") (pin "21") (pinfunction "B1_21") (pintype "input"))
    )
    (net (code "18") (name "/FPGA_DONE") (class "Default")
      (node (ref "P18T") (pin "11") (pinfunction "11_11") (pintype "passive"))
      (node (ref "U15T") (pin "4") (pinfunction "A2_4") (pintype "bidirectional"))
    )
    (net (code "19") (name "/FPGA_INIT") (class "Default")
      (node (ref "P18T") (pin "15") (pinfunction "15_15") (pintype "passive"))
      (node (ref "U15T") (pin "5") (pinfunction "A3_5") (pintype "bidirectional"))
    )
    (net (code "20") (name "/FPGA_PROGRAM_B") (class "Default")
      (node (ref "P18T") (pin "17") (pinfunction "17_17") (pintype "passive"))
      (node (ref "U12T") (pin "3") (pinfunction "A1_3") (pintype "bidirectional"))
    )
    (net (code "21") (name "/FPGA_TCK") (class "Default")
      (node (ref "C10T") (pin "2") (pinfunction "2_2") (pintype "passive"))
      (node (ref "P18T") (pin "8") (pinfunction "8_8") (pintype "passive"))
      (node (ref "R10T") (pin "1") (pinfunction "1_1") (pintype "passive"))
      (node (ref "R11T") (pin "2") (pinfunction "2_2") (pintype "passive"))
    )
    (net (code "22") (name "/FPGA_TCK_R") (class "Default")
      (node (ref "R10T") (pin "2") (pinfunction "2_2") (pintype "passive"))
      (node (ref "U12T") (pin "7") (pinfunction "A5_7") (pintype "bidirectional"))
    )
    (net (code "23") (name "/FPGA_TDI") (class "Default")
      (node (ref "C15T") (pin "2") (pinfunction "2_2") (pintype "passive"))
      (node (ref "P18T") (pin "14") (pinfunction "14_14") (pintype "passive"))
      (node (ref "R14T") (pin "1") (pinfunction "1_1") (pintype "passive"))
      (node (ref "R17T") (pin "2") (pinfunction "2_2") (pintype "passive"))
    )
    (net (code "24") (name "/FPGA_TDI_R") (class "Default")
      (node (ref "R14T") (pin "2") (pinfunction "2_2") (pintype "passive"))
      (node (ref "U12T") (pin "4") (pinfunction "A2_4") (pintype "bidirectional"))
    )
    (net (code "25") (name "/FPGA_TDO") (class "Default")
      (node (ref "P18T") (pin "16") (pinfunction "16_16") (pintype "passive"))
      (node (ref "U15T") (pin "6") (pinfunction "A4_6") (pintype "bidirectional"))
    )
    (net (code "26") (name "/FPGA_TMS") (class "Default")
      (node (ref "C16T") (pin "2") (pinfunction "2_2") (pintype "passive"))
      (node (ref "P18T") (pin "12") (pinfunction "12_12") (pintype "passive"))
      (node (ref "R15T") (pin "1") (pinfunction "1_1") (pintype "passive"))
      (node (ref "R18T") (pin "2") (pinfunction "2_2") (pintype "passive"))
    )
    (net (code "27") (name "/FPGA_TMS_R") (class "Default")
      (node (ref "R15T") (pin "2") (pinfunction "2_2") (pintype "passive"))
      (node (ref "U12T") (pin "5") (pinfunction "A3_5") (pintype "bidirectional"))
    )
    (net (code "28") (name "/I12V_ADC") (class "Default")
      (node (ref "C31T") (pin "1") (pinfunction "1_1") (pintype "passive"))
      (node (ref "R47T") (pin "2") (pinfunction "2_2") (pintype "passive"))
      (node (ref "U13T") (pin "9") (pinfunction "IN7_9") (pintype "input"))
    )
    (net (code "29") (name "/I12V_BUF") (class "Default")
      (node (ref "R47T") (pin "1") (pinfunction "1_1") (pintype "passive"))
      (node (ref "U16T") (pin "1") (pinfunction "OUT_1") (pintype "output"))
      (node (ref "U16T") (pin "4") (pinfunction "IN-_4") (pintype "input"))
    )
    (net (code "30") (name "/I12V_SENSE") (class "Default")
      (node (ref "R43T") (pin "1") (pinfunction "1_1") (pintype "passive"))
      (node (ref "U14T") (pin "1") (pinfunction "OUT_1") (pintype "output"))
      (node (ref "U16T") (pin "3") (pinfunction "IN+_3") (pintype "input"))
    )
    (net (code "31") (name "/LDOA_CC") (class "Default")
      (node (ref "C37T") (pin "2") (pinfunction "2_2") (pintype "passive"))
      (node (ref "U18T") (pin "6") (pinfunction "CC_6") (pintype "passive"))
    )
    (net (code "32") (name "/LDOD_CC") (class "Default")
      (node (ref "C38T") (pin "2") (pinfunction "2_2") (pintype "passive"))
      (node (ref "U19T") (pin "6") (pinfunction "CC_6") (pintype "passive"))
    )
    (net (code "33") (name "/LED0") (class "Default")
      (node (ref "P17T") (pin "3") (pinfunction "3_3") (pintype "passive"))
      (node (ref "R54T") (pin "2") (pinfunction "2_2") (pintype "passive"))
    )
    (net (code "34") (name "/LED0_R") (class "Default")
      (node (ref "P19T") (pin "1") (pinfunction "1_1") (pintype "passive"))
      (node (ref "R54T") (pin "1") (pinfunction "1_1") (pintype "passive"))
    )
    (net (code "35") (name "/LED1") (class "Default")
      (node (ref "P17T") (pin "5") (pinfunction "5_5") (pintype "passive"))
      (node (ref "R55T") (pin "2") (pinfunction "2_2") (pintype "passive"))
    )
    (net (code "36") (name "/LED1_R") (class "Default")
      (node (ref "P19T") (pin "2") (pinfunction "2_2") (pintype "passive"))
      (node (ref "R55T") (pin "1") (pinfunction "1_1") (pintype "passive"))
    )
    (net (code "37") (name "/LED2") (class "Default")
      (node (ref "P17T") (pin "7") (pinfunction "7_7") (pintype "passive"))
      (node (ref "R57T") (pin "2") (pinfunction "2_2") (pintype "passive"))
    )
    (net (code "38") (name "/LED2_R") (class "Default")
      (node (ref "P22T") (pin "1") (pinfunction "1_1") (pintype "passive"))
      (node (ref "R57T") (pin "1") (pinfunction "1_1") (pintype "passive"))
    )
    (net (code "39") (name "/P0.75VTT") (class "Default")
      (node (ref "P16T") (pin "1") (pinfunction "1_1") (pintype "passive"))
      (node (ref "R60T") (pin "1") (pinfunction "1_1") (pintype "passive"))
    )
    (net (code "40") (name "/P0.75VTT_ADC") (class "Default")
      (node (ref "D19T") (pin "2") (pinfunction "A_2") (pintype "passive"))
      (node (ref "R60T") (pin "2") (pinfunction "2_2") (pintype "passive"))
      (node (ref "R61T") (pin "1") (pinfunction "1_1") (pintype "passive"))
      (node (ref "U13T") (pin "15") (pinfunction "IN1_15") (pintype "input"))
    )
    (net (code "41") (name "/P1.0V") (class "Default")
      (node (ref "P16T") (pin "2") (pinfunction "2_2") (pintype "passive"))
      (node (ref "R52T") (pin "1") (pinfunction "1_1") (pintype "passive"))
    )
    (net (code "42") (name "/P1.0V_ADC") (class "Default")
      (node (ref "D18T") (pin "2") (pinfunction "A_2") (pintype "passive"))
      (node (ref "R52T") (pin "2") (pinfunction "2_2") (pintype "passive"))
      (node (ref "R53T") (pin "1") (pinfunction "1_1") (pintype "passive"))
      (node (ref "U13T") (pin "16") (pinfunction "IN0_16") (pintype "input"))
    )
    (net (code "43") (name "/P1.2E_SENSE") (class "Default")
      (node (ref "P15T") (pin "1") (pinfunction "1_1") (pintype "passive"))
      (node (ref "R48T") (pin "1") (pinfunction "1_1") (pintype "passive"))
    )
    (net (code "44") (name "/P1.2VE_ADC") (class "Default")
      (node (ref "D17T") (pin "2") (pinfunction "A_2") (pintype "passive"))
      (node (ref "R48T") (pin "2") (pinfunction "2_2") (pintype "passive"))
      (node (ref "R49T") (pin "1") (pinfunction "1_1") (pintype "passive"))
      (node (ref "U11T") (pin "15") (pinfunction "IN1_15") (pintype "input"))
    )
    (net (code "45") (name "/P1.2VTT_ADC") (class "Default")
      (node (ref "D16T") (pin "2") (pinfunction "A_2") (pintype "passive"))
      (node (ref "R45T") (pin "2") (pinfunction "2_2") (pintype "passive"))
      (node (ref "R46T") (pin "1") (pinfunction "1_1") (pintype "passive"))
      (node (ref "U11T") (pin "16") (pinfunction "IN0_16") (pintype "input"))
    )
    (net (code "46") (name "/P1.2VTT_SENSE") (class "Default")
      (node (ref "P15T") (pin "2") (pinfunction "2_2") (pintype "passive"))
      (node (ref "R45T") (pin "1") (pinfunction "1_1") (pintype "passive"))
    )
    (net (code "47") (name "/P1.5V_ADC") (class "Default")
      (node (ref "D15T") (pin "2") (pinfunction "A_2") (pintype "passive"))
      (node (ref "R41T") (pin "2") (pinfunction "2_2") (pintype "passive"))
      (node (ref "R42T") (pin "1") (pinfunction "1_1") (pintype "passive"))
      (node (ref "U11T") (pin "13") (pinfunction "IN3_13") (pintype "input"))
    )
    (net (code "48") (name "/P1.5V_SENSE") (class "Default")
      (node (ref "P14T") (pin "1") (pinfunction "1_1") (pintype "passive"))
      (node (ref "R41T") (pin "1") (pinfunction "1_1") (pintype "passive"))
    )
    (net (code "49") (name "/P1.8V_ADC") (class "Default")
      (node (ref "D14T") (pin "2") (pinfunction "A_2") (pintype "passive"))
      (node (ref "R39T") (pin "2") (pinfunction "2_2") (pintype "passive"))
      (node (ref "R40T") (pin "1") (pinfunction "1_1") (pintype "passive"))
      (node (ref "U11T") (pin "14") (pinfunction "IN2_14") (pintype "input"))
    )
    (net (code "50") (name "/P1.8V_SENSE") (class "Default")
      (node (ref "P14T") (pin "2") (pinfunction "2_2") (pintype "passive"))
      (node (ref "R39T") (pin "1") (pinfunction "1_1") (pintype "passive"))
    )
    (net (code "51") (name "/P3.3VE_ADC") (class "Default")
      (node (ref "D13T") (pin "2") (pinfunction "A_2") (pintype "passive"))
      (node (ref "R33T") (pin "2") (pinfunction "2_2") (pintype "passive"))
      (node (ref "R34T") (pin "1") (pinfunction "1_1") (pintype "passive"))
      (node (ref "U11T") (pin "11") (pinfunction "IN5_11") (pintype "input"))
    )
    (net (code "52") (name "/P3.3VE_SENSE") (class "Default")
      (node (ref "P13T") (pin "1") (pinfunction "1_1") (pintype "passive"))
      (node (ref "R33T") (pin "1") (pinfunction "1_1") (pintype "passive"))
    )
    (net (code "53") (name "/P3.3V_ADC") (class "Default")
      (node (ref "D12T") (pin "2") (pinfunction "A_2") (pintype "passive"))
      (node (ref "R24T") (pin "2") (pinfunction "2_2") (pintype "passive"))
      (node (ref "R25T") (pin "1") (pinfunction "1_1") (pintype "passive"))
      (node (ref "U11T") (pin "12") (pinfunction "IN4_12") (pintype "input"))
    )
    (net (code "54") (name "/P3.3V_SENSE") (class "Default")
      (node (ref "P13T") (pin "2") (pinfunction "2_2") (pintype "passive"))
      (node (ref "R24T") (pin "1") (pinfunction "1_1") (pintype "passive"))
    )
    (net (code "55") (name "/P5V_ADC") (class "Default")
      (node (ref "D11T") (pin "2") (pinfunction "A_2") (pintype "passive"))
      (node (ref "R19T") (pin "2") (pinfunction "2_2") (pintype "passive"))
      (node (ref "R20T") (pin "1") (pinfunction "1_1") (pintype "passive"))
      (node (ref "U11T") (pin "10") (pinfunction "IN6_10") (pintype "input"))
    )
    (net (code "56") (name "/P5V_SENSE") (class "Default")
      (node (ref "P12T") (pin "1") (pinfunction "1_1") (pintype "passive"))
      (node (ref "R19T") (pin "1") (pinfunction "1_1") (pintype "passive"))
    )
    (net (code "57") (name "/P12V_ADC") (class "Default")
      (node (ref "D10T") (pin "2") (pinfunction "A_2") (pintype "passive"))
      (node (ref "R12T") (pin "2") (pinfunction "2_2") (pintype "passive"))
      (node (ref "R13T") (pin "1") (pinfunction "1_1") (pintype "passive"))
      (node (ref "U11T") (pin "9") (pinfunction "IN7_9") (pintype "input"))
    )
    (net (code "58") (name "/P12V_DUT") (class "Default")
      (node (ref "JDUT") (pin "A2") (pinfunction "A2_A2") (pintype "passive"))
      (node (ref "JDUT") (pin "A3") (pinfunction "A3_A3") (pintype "passive"))
      (node (ref "JDUT") (pin "B1") (pinfunction "B1_B1") (pintype "passive"))
      (node (ref "JDUT") (pin "B2") (pinfunction "B2_B2") (pintype "passive"))
      (node (ref "JDUT") (pin "B3") (pinfunction "B3_B3") (pintype "passive"))
      (node (ref "P10T") (pin "1") (pinfunction "1_1") (pintype "passive"))
      (node (ref "R26T") (pin "2") (pinfunction "2_2") (pintype "passive"))
      (node (ref "R27T") (pin "1") (pinfunction "1_1") (pintype "passive"))
      (node (ref "U14T") (pin "4") (pinfunction "VIN-_4") (pintype "input"))
    )
    (net (code "59") (name "/P12V_DUT_ISENSE") (class "Default")
      (node (ref "C13T") (pin "2") (pinfunction "2_2") (pintype "passive"))
      (node (ref "C22T") (pin "2") (pinfunction "2_2") (pintype "passive"))
      (node (ref "Q10T") (pin "2") (pinfunction "D_2") (pintype "passive"))
      (node (ref "Q10T") (pin "3") (pinfunction "D_3") (pintype "passive"))
      (node (ref "R26T") (pin "1") (pinfunction "1_1") (pintype "passive"))
      (node (ref "U10T") (pin "3") (pinfunction "IN_3") (pintype "power_in"))
      (node (ref "U14T") (pin "3") (pinfunction "VIN+_3") (pintype "input"))
    )
    (net (code "60") (name "/P12V_SENSE") (class "Default")
      (node (ref "P11T") (pin "1") (pinfunction "1_1") (pintype "passive"))
      (node (ref "R12T") (pin "1") (pinfunction "1_1") (pintype "passive"))
    )
    (net (code "61") (name "/PCI_PRESENT") (class "Default")
      (node (ref "JDUT") (pin "B31") (pinfunction "B31_B31") (pintype "passive"))
      (node (ref "P17T") (pin "12") (pinfunction "12_12") (pintype "passive"))
      (node (ref "R44T") (pin "1") (pinfunction "1_1") (pintype "passive"))
    )
    (net (code "62") (name "/PET0_N") (class "Default")
      (node (ref "JDUT") (pin "A17") (pinfunction "A17_A17") (pintype "passive"))
      (node (ref "JDUT") (pin "B15") (pinfunction "B15_B15") (pintype "passive"))
    )
    (net (code "63") (name "/PET0_P") (class "Default")
      (node (ref "JDUT") (pin "A16") (pinfunction "A16_A16") (pintype "passive"))
      (node (ref "JDUT") (pin "B14") (pinfunction "B14_B14") (pintype "passive"))
    )
    (net (code "64") (name "/PET1_N") (class "Default")
      (node (ref "JDUT") (pin "A22") (pinfunction "A22_A22") (pintype "passive"))
      (node (ref "JDUT") (pin "B20") (pinfunction "B20_B20") (pintype "passive"))
    )
    (net (code "65") (name "/PET1_P") (class "Default")
      (node (ref "JDUT") (pin "A21") (pinfunction "A21_A21") (pintype "passive"))
      (node (ref "JDUT") (pin "B19") (pinfunction "B19_B19") (pintype "passive"))
    )
    (net (code "66") (name "/PET2_N") (class "Default")
      (node (ref "JDUT") (pin "A26") (pinfunction "A26_A26") (pintype "passive"))
      (node (ref "JDUT") (pin "B24") (pinfunction "B24_B24") (pintype "passive"))
    )
    (net (code "67") (name "/PET2_P") (class "Default")
      (node (ref "JDUT") (pin "A25") (pinfunction "A25_A25") (pintype "passive"))
      (node (ref "JDUT") (pin "B23") (pinfunction "B23_B23") (pintype "passive"))
    )
    (net (code "68") (name "/PET3_N") (class "Default")
      (node (ref "JDUT") (pin "A30") (pinfunction "A30_A30") (pintype "passive"))
      (node (ref "JDUT") (pin "B28") (pinfunction "B28_B28") (pintype "passive"))
    )
    (net (code "69") (name "/PET3_P") (class "Default")
      (node (ref "JDUT") (pin "A29") (pinfunction "A29_A29") (pintype "passive"))
      (node (ref "JDUT") (pin "B27") (pinfunction "B27_B27") (pintype "passive"))
    )
    (net (code "70") (name "/REFCLK_N") (class "Default")
      (node (ref "JDUT") (pin "A14") (pinfunction "A14_A14") (pintype "passive"))
      (node (ref "R66T") (pin "1") (pinfunction "1_1") (pintype "passive"))
      (node (ref "U17T") (pin "4") (pinfunction "OUT_4") (pintype "output"))
    )
    (net (code "71") (name "/REFCLK_P") (class "Default")
      (node (ref "JDUT") (pin "A13") (pinfunction "A13_A13") (pintype "passive"))
      (node (ref "R67T") (pin "1") (pinfunction "1_1") (pintype "passive"))
      (node (ref "U17T") (pin "5") (pinfunction "~{OUT}_5") (pintype "output"))
    )
    (net (code "72") (name "/RPI_ADCINT") (class "Default")
      (node (ref "P17T") (pin "15") (pinfunction "15_15") (pintype "passive"))
      (node (ref "R16T") (pin "1") (pinfunction "1_1") (pintype "passive"))
      (node (ref "U11T") (pin "6") (pinfunction "~{INT}_6") (pintype "output"))
      (node (ref "U13T") (pin "6") (pinfunction "~{INT}_6") (pintype "output"))
    )
    (net (code "73") (name "/RPI_SCL") (class "Default")
      (node (ref "P18T") (pin "6") (pinfunction "6_6") (pintype "passive"))
      (node (ref "R31T") (pin "1") (pinfunction "1_1") (pintype "passive"))
      (node (ref "U11T") (pin "3") (pinfunction "SCL_3") (pintype "input"))
      (node (ref "U13T") (pin "3") (pinfunction "SCL_3") (pintype "input"))
    )
    (net (code "74") (name "/RPI_SDA") (class "Default")
      (node (ref "P18T") (pin "4") (pinfunction "4_4") (pintype "passive"))
      (node (ref "R32T") (pin "1") (pinfunction "1_1") (pintype "passive"))
      (node (ref "U11T") (pin "2") (pinfunction "SDA_2") (pintype "bidirectional"))
      (node (ref "U13T") (pin "2") (pinfunction "SDA_2") (pintype "bidirectional"))
    )
    (net (code "75") (name "/SCENARIO") (class "Default")
      (node (ref "P17T") (pin "10") (pinfunction "10_10") (pintype "passive"))
      (node (ref "P21T") (pin "2") (pinfunction "2_2") (pintype "passive"))
    )
    (net (code "76") (name "/SS5.0") (class "Default")
      (node (ref "C48T") (pin "1") (pinfunction "1_1") (pintype "passive"))
      (node (ref "U20T") (pin "4") (pinfunction "SS_4") (pintype "passive"))
    )
    (net (code "77") (name "/SW5.0") (class "Default")
      (node (ref "C45T") (pin "1") (pinfunction "1_1") (pintype "passive"))
      (node (ref "L10T") (pin "1") (pinfunction "1_1") (pintype "passive"))
      (node (ref "U20T") (pin "6") (pinfunction "SW_6") (pintype "output"))
    )
    (net (code "78") (name "/UART0_RX") (class "Default")
      (node (ref "P18T") (pin "7") (pinfunction "7_7") (pintype "passive"))
      (node (ref "U12T") (pin "6") (pinfunction "A4_6") (pintype "bidirectional"))
    )
    (net (code "79") (name "/UART0_TX") (class "Default")
      (node (ref "P18T") (pin "9") (pinfunction "9_9") (pintype "passive"))
      (node (ref "U15T") (pin "3") (pinfunction "A1_3") (pintype "bidirectional"))
    )
    (net (code "80") (name "/VFB5.0") (class "Default")
      (node (ref "C39T") (pin "2") (pinfunction "2_2") (pintype "passive"))
      (node (ref "R62T") (pin "1") (pinfunction "1_1") (pintype "passive"))
      (node (ref "R63T") (pin "2") (pinfunction "2_2") (pintype "passive"))
      (node (ref "U20T") (pin "2") (pinfunction "VFB_2") (pintype "input"))
    )
    (net (code "81") (name "/VREG5.0") (class "Default")
      (node (ref "C49T") (pin "1") (pinfunction "1_1") (pintype "passive"))
      (node (ref "U20T") (pin "3") (pinfunction "VREG5_3") (pintype "power_in"))
    )
    (net (code "82") (name "GND") (class "Default")
      (node (ref "C10T") (pin "1") (pinfunction "1_1") (pintype "passive"))
      (node (ref "C11T") (pin "2") (pinfunction "2_2") (pintype "passive"))
      (node (ref "C12T") (pin "2") (pinfunction "2_2") (pintype "passive"))
      (node (ref "C13T") (pin "1") (pinfunction "1_1") (pintype "passive"))
      (node (ref "C14T") (pin "2") (pinfunction "2_2") (pintype "passive"))
      (node (ref "C15T") (pin "1") (pinfunction "1_1") (pintype "passive"))
      (node (ref "C16T") (pin "1") (pinfunction "1_1") (pintype "passive"))
      (node (ref "C17T") (pin "2") (pinfunction "2_2") (pintype "passive"))
      (node (ref "C18T") (pin "2") (pinfunction "2_2") (pintype "passive"))
      (node (ref "C19T") (pin "2") (pinfunction "2_2") (pintype "passive"))
      (node (ref "C20T") (pin "2") (pinfunction "2_2") (pintype "passive"))
      (node (ref "C21T") (pin "1") (pinfunction "1_1") (pintype "passive"))
      (node (ref "C22T") (pin "1") (pinfunction "1_1") (pintype "passive"))
      (node (ref "C23T") (pin "1") (pinfunction "1_1") (pintype "passive"))
      (node (ref "C24T") (pin "1") (pinfunction "1_1") (pintype "passive"))
      (node (ref "C25T") (pin "1") (pinfunction "1_1") (pintype "passive"))
      (node (ref "C26T") (pin "2") (pinfunction "2_2") (pintype "passive"))
      (node (ref "C27T") (pin "2") (pinfunction "2_2") (pintype "passive"))
      (node (ref "C28T") (pin "2") (pinfunction "2_2") (pintype "passive"))
      (node (ref "C29T") (pin "2") (pinfunction "2_2") (pintype "passive"))
      (node (ref "C30T") (pin "2") (pinfunction "2_2") (pintype "passive"))
      (node (ref "C31T") (pin "2") (pinfunction "2_2") (pintype "passive"))
      (node (ref "C32T") (pin "1") (pinfunction "1_1") (pintype "passive"))
      (node (ref "C33T") (pin "2") (pinfunction "2_2") (pintype "passive"))
      (node (ref "C34T") (pin "2") (pinfunction "2_2") (pintype "passive"))
      (node (ref "C35T") (pin "2") (pinfunction "2_2") (pintype "passive"))
      (node (ref "C36T") (pin "2") (pinfunction "2_2") (pintype "passive"))
      (node (ref "C37T") (pin "1") (pinfunction "1_1") (pintype "passive"))
      (node (ref "C38T") (pin "1") (pinfunction "1_1") (pintype "passive"))
      (node (ref "C40T") (pin "2") (pinfunction "2_2") (pintype "passive"))
      (node (ref "C41T") (pin "1") (pinfunction "1_1") (pintype "passive"))
      (node (ref "C42T") (pin "1") (pinfunction "1_1") (pintype "passive"))
      (node (ref "C43T") (pin "2") (pinfunction "2_2") (pintype "passive"))
      (node (ref "C44T") (pin "2") (pinfunction "2_2") (pintype "passive"))
      (node (ref "C46T") (pin "2") (pinfunction "2_2") (pintype "passive"))
      (node (ref "C47T") (pin "2") (pinfunction "2_2") (pintype "passive"))
      (node (ref "C48T") (pin "2") (pinfunction "2_2") (pintype "passive"))
      (node (ref "C49T") (pin "2") (pinfunction "2_2") (pintype "passive"))
      (node (ref "D21T") (pin "2") (pinfunction "K_2") (pintype "passive"))
      (node (ref "JDUT") (pin "A12") (pinfunction "A12_A12") (pintype "passive"))
      (node (ref "JDUT") (pin "A15") (pinfunction "A15_A15") (pintype "passive"))
      (node (ref "JDUT") (pin "A18") (pinfunction "A18_A18") (pintype "passive"))
      (node (ref "JDUT") (pin "A20") (pinfunction "A20_A20") (pintype "passive"))
      (node (ref "JDUT") (pin "A23") (pinfunction "A23_A23") (pintype "passive"))
      (node (ref "JDUT") (pin "A24") (pinfunction "A24_A24") (pintype "passive"))
      (node (ref "JDUT") (pin "A27") (pinfunction "A27_A27") (pintype "passive"))
      (node (ref "JDUT") (pin "A28") (pinfunction "A28_A28") (pintype "passive"))
      (node (ref "JDUT") (pin "A31") (pinfunction "A31_A31") (pintype "passive"))
      (node (ref "JDUT") (pin "A4") (pinfunction "A4_A4") (pintype "passive"))
      (node (ref "JDUT") (pin "B13") (pinfunction "B13_B13") (pintype "passive"))
      (node (ref "JDUT") (pin "B16") (pinfunction "B16_B16") (pintype "passive"))
      (node (ref "JDUT") (pin "B18") (pinfunction "B18_B18") (pintype "passive"))
      (node (ref "JDUT") (pin "B21") (pinfunction "B21_B21") (pintype "passive"))
      (node (ref "JDUT") (pin "B22") (pinfunction "B22_B22") (pintype "passive"))
      (node (ref "JDUT") (pin "B25") (pinfunction "B25_B25") (pintype "passive"))
      (node (ref "JDUT") (pin "B26") (pinfunction "B26_B26") (pintype "passive"))
      (node (ref "JDUT") (pin "B29") (pinfunction "B29_B29") (pintype "passive"))
      (node (ref "JDUT") (pin "B32") (pinfunction "B32_B32") (pintype "passive"))
      (node (ref "JDUT") (pin "B4") (pinfunction "B4_B4") (pintype "passive"))
      (node (ref "JDUT") (pin "B7") (pinfunction "B7_B7") (pintype "passive"))
      (node (ref "JP10T") (pin "2") (pintype "power_in"))
      (node (ref "JP10T") (pin "3") (pintype "power_in"))
      (node (ref "JPI") (pin "A12") (pinfunction "A12_A12") (pintype "passive"))
      (node (ref "JPI") (pin "A15") (pinfunction "A15_A15") (pintype "passive"))
      (node (ref "JPI") (pin "A18") (pinfunction "A18_A18") (pintype "passive"))
      (node (ref "JPI") (pin "A20") (pinfunction "A20_A20") (pintype "passive"))
      (node (ref "JPI") (pin "A23") (pinfunction "A23_A23") (pintype "passive"))
      (node (ref "JPI") (pin "A24") (pinfunction "A24_A24") (pintype "passive"))
      (node (ref "JPI") (pin "A27") (pinfunction "A27_A27") (pintype "passive"))
      (node (ref "JPI") (pin "A28") (pinfunction "A28_A28") (pintype "passive"))
      (node (ref "JPI") (pin "A31") (pinfunction "A31_A31") (pintype "passive"))
      (node (ref "JPI") (pin "B13") (pinfunction "B13_B13") (pintype "passive"))
      (node (ref "JPI") (pin "B16") (pinfunction "B16_B16") (pintype "passive"))
      (node (ref "JPI") (pin "B18") (pinfunction "B18_B18") (pintype "passive"))
      (node (ref "JPI") (pin "B21") (pinfunction "B21_B21") (pintype "passive"))
      (node (ref "JPI") (pin "B22") (pinfunction "B22_B22") (pintype "passive"))
      (node (ref "JPI") (pin "B25") (pinfunction "B25_B25") (pintype "passive"))
      (node (ref "JPI") (pin "B26") (pinfunction "B26_B26") (pintype "passive"))
      (node (ref "JPI") (pin "B29") (pinfunction "B29_B29") (pintype "passive"))
      (node (ref "JPI") (pin "B32") (pinfunction "B32_B32") (pintype "passive"))
      (node (ref "JPI") (pin "B4") (pinfunction "B4_B4") (pintype "passive"))
      (node (ref "JPI") (pin "B7") (pinfunction "B7_B7") (pintype "passive"))
      (node (ref "P10T") (pin "2") (pinfunction "2_2") (pintype "passive"))
      (node (ref "P11T") (pin "2") (pinfunction "2_2") (pintype "passive"))
      (node (ref "P12T") (pin "2") (pinfunction "2_2") (pintype "passive"))
      (node (ref "P17T") (pin "13") (pinfunction "13_13") (pintype "passive"))
      (node (ref "P17T") (pin "20") (pinfunction "20_20") (pintype "passive"))
      (node (ref "P17T") (pin "6") (pinfunction "6_6") (pintype "passive"))
      (node (ref "P17T") (pin "9") (pinfunction "9_9") (pintype "passive"))
      (node (ref "P18T") (pin "10") (pinfunction "10_10") (pintype "passive"))
      (node (ref "P18T") (pin "13") (pinfunction "13_13") (pintype "passive"))
      (node (ref "P18T") (pin "19") (pinfunction "19_19") (pintype "passive"))
      (node (ref "P18T") (pin "5") (pinfunction "5_5") (pintype "passive"))
      (node (ref "P21T") (pin "3") (pinfunction "3_3") (pintype "passive"))
      (node (ref "P22T") (pin "2") (pinfunction "2_2") (pintype "passive"))
      (node (ref "P26T") (pin "2") (pinfunction "2_2") (pintype "passive"))
      (node (ref "Q11T") (pin "2") (pinfunction "S_2") (pintype "passive"))
      (node (ref "R11T") (pin "1") (pinfunction "1_1") (pintype "passive"))
      (node (ref "R13T") (pin "2") (pinfunction "2_2") (pintype "passive"))
      (node (ref "R17T") (pin "1") (pinfunction "1_1") (pintype "passive"))
      (node (ref "R18T") (pin "1") (pinfunction "1_1") (pintype "passive"))
      (node (ref "R20T") (pin "2") (pinfunction "2_2") (pintype "passive"))
      (node (ref "R21T") (pin "2") (pinfunction "2_2") (pintype "passive"))
      (node (ref "R22T") (pin "2") (pinfunction "2_2") (pintype "passive"))
      (node (ref "R23T") (pin "2") (pinfunction "2_2") (pintype "passive"))
      (node (ref "R25T") (pin "2") (pinfunction "2_2") (pintype "passive"))
      (node (ref "R27T") (pin "2") (pinfunction "2_2") (pintype "passive"))
      (node (ref "R34T") (pin "2") (pinfunction "2_2") (pintype "passive"))
      (node (ref "R38T") (pin "2") (pinfunction "2_2") (pintype "passive"))
      (node (ref "R40T") (pin "2") (pinfunction "2_2") (pintype "passive"))
      (node (ref "R42T") (pin "2") (pinfunction "2_2") (pintype "passive"))
      (node (ref "R43T") (pin "2") (pinfunction "2_2") (pintype "passive"))
      (node (ref "R44T") (pin "2") (pinfunction "2_2") (pintype "passive"))
      (node (ref "R46T") (pin "2") (pinfunction "2_2") (pintype "passive"))
      (node (ref "R49T") (pin "2") (pinfunction "2_2") (pintype "passive"))
      (node (ref "R51T") (pin "1") (pinfunction "1_1") (pintype "passive"))
      (node (ref "R53T") (pin "2") (pinfunction "2_2") (pintype "passive"))
      (node (ref "R56T") (pin "2") (pinfunction "2_2") (pintype "passive"))
      (node (ref "R61T") (pin "2") (pinfunction "2_2") (pintype "passive"))
      (node (ref "R63T") (pin "1") (pinfunction "1_1") (pintype "passive"))
      (node (ref "R64T") (pin "2") (pinfunction "2_2") (pintype "passive"))
      (node (ref "R65T") (pin "1") (pinfunction "1_1") (pintype "passive"))
      (node (ref "R66T") (pin "2") (pinfunction "2_2") (pintype "passive"))
      (node (ref "R67T") (pin "2") (pinfunction "2_2") (pintype "passive"))
      (node (ref "U10T") (pin "1") (pinfunction "GND_1") (pintype "power_in"))
      (node (ref "U11T") (pin "4") (pinfunction "GND_4") (pintype "power_in"))
      (node (ref "U12T") (pin "10") (pinfunction "A8_10") (pintype "bidirectional"))
      (node (ref "U12T") (pin "11") (pinfunction "GND_11") (pintype "power_in"))
      (node (ref "U12T") (pin "12") (pinfunction "GND_12") (pintype "power_in"))
      (node (ref "U12T") (pin "13") (pinfunction "GND_13") (pintype "power_in"))
      (node (ref "U12T") (pin "22") (pinfunction "~{OE}_22") (pintype "input"))
      (node (ref "U12T") (pin "8") (pinfunction "A6_8") (pintype "bidirectional"))
      (node (ref "U12T") (pin "9") (pinfunction "A7_9") (pintype "bidirectional"))
      (node (ref "U13T") (pin "4") (pinfunction "GND_4") (pintype "power_in"))
      (node (ref "U14T") (pin "2") (pinfunction "GND_2") (pintype "power_in"))
      (node (ref "U15T") (pin "11") (pinfunction "GND_11") (pintype "power_in"))
      (node (ref "U15T") (pin "12") (pinfunction "GND_12") (pintype "power_in"))
      (node (ref "U15T") (pin "13") (pinfunction "GND_13") (pintype "power_in"))
      (node (ref "U15T") (pin "14") (pinfunction "B8_14") (pintype "input"))
      (node (ref "U15T") (pin "15") (pinfunction "B7_15") (pintype "input"))
      (node (ref "U15T") (pin "16") (pinfunction "B6_16") (pintype "input"))
      (node (ref "U15T") (pin "17") (pinfunction "B5_17") (pintype "input"))
      (node (ref "U15T") (pin "2") (pinfunction "DIR_2") (pintype "input"))
      (node (ref "U15T") (pin "22") (pinfunction "~{OE}_22") (pintype "input"))
      (node (ref "U16T") (pin "2") (pinfunction "V-_2") (pintype "power_in"))
      (node (ref "U17T") (pin "3") (pinfunction "GND_3") (pintype "power_in"))
      (node (ref "U18T") (pin "3") (pinfunction "GND_3") (pintype "power_in"))
      (node (ref "U19T") (pin "3") (pinfunction "GND_3") (pintype "power_in"))
      (node (ref "U20T") (pin "5") (pinfunction "GND_5") (pintype "power_in"))
      (node (ref "U20T") (pin "9") (pinfunction "GND-EP_9") (pintype "power_in"))
    )
    (net (code "83") (name "Net-(D20T-K)") (class "Default")
      (node (ref "D20T") (pin "2") (pinfunction "K_2") (pintype "passive"))
      (node (ref "R64T") (pin "1") (pinfunction "1_1") (pintype "passive"))
    )
    (net (code "84") (name "Net-(JDUT-PadA5)") (class "Default")
      (node (ref "JDUT") (pin "A5") (pinfunction "A5_A5") (pintype "passive"))
      (node (ref "JDUT") (pin "A6") (pinfunction "A6_A6") (pintype "passive"))
    )
    (net (code "85") (name "Net-(JDUT-PadA7)") (class "Default")
      (node (ref "JDUT") (pin "A7") (pinfunction "A7_A7") (pintype "passive"))
      (node (ref "JDUT") (pin "A8") (pinfunction "A8_A8") (pintype "passive"))
    )
    (net (code "86") (name "Net-(JDUT-PadA10)") (class "Default")
      (node (ref "JDUT") (pin "A10") (pinfunction "A10_A10") (pintype "passive"))
      (node (ref "JDUT") (pin "A9") (pinfunction "A9_A9") (pintype "passive"))
    )
    (net (code "87") (name "Net-(JDUT-PadA11)") (class "Default")
      (node (ref "JDUT") (pin "A11") (pinfunction "A11_A11") (pintype "passive"))
      (node (ref "JDUT") (pin "B12") (pinfunction "B12_B12") (pintype "passive"))
    )
    (net (code "88") (name "Net-(JDUT-PadB5)") (class "Default")
      (node (ref "JDUT") (pin "B5") (pinfunction "B5_B5") (pintype "passive"))
      (node (ref "JDUT") (pin "B6") (pinfunction "B6_B6") (pintype "passive"))
    )
    (net (code "89") (name "Net-(JDUT-PadB8)") (class "Default")
      (node (ref "JDUT") (pin "B8") (pinfunction "B8_B8") (pintype "passive"))
      (node (ref "JDUT") (pin "B9") (pinfunction "B9_B9") (pintype "passive"))
    )
    (net (code "90") (name "Net-(JDUT-PadB10)") (class "Default")
      (node (ref "JDUT") (pin "B10") (pinfunction "B10_B10") (pintype "passive"))
      (node (ref "JDUT") (pin "B11") (pinfunction "B11_B11") (pintype "passive"))
    )
    (net (code "91") (name "Net-(Q10T-G)") (class "Default")
      (node (ref "Q10T") (pin "1") (pinfunction "G_1") (pintype "passive"))
      (node (ref "Q11T") (pin "3") (pinfunction "D_3") (pintype "passive"))
      (node (ref "R36T") (pin "1") (pinfunction "1_1") (pintype "passive"))
    )
    (net (code "92") (name "Net-(U11T-A0)") (class "Default")
      (node (ref "R23T") (pin "1") (pinfunction "1_1") (pintype "passive"))
      (node (ref "U11T") (pin "7") (pinfunction "A0_7") (pintype "input"))
    )
    (net (code "93") (name "Net-(U11T-A1)") (class "Default")
      (node (ref "R21T") (pin "1") (pinfunction "1_1") (pintype "passive"))
      (node (ref "U11T") (pin "8") (pinfunction "A1_8") (pintype "input"))
    )
    (net (code "94") (name "Net-(U13T-A0)") (class "Default")
      (node (ref "R37T") (pin "1") (pinfunction "1_1") (pintype "passive"))
      (node (ref "U13T") (pin "7") (pinfunction "A0_7") (pintype "input"))
    )
    (net (code "95") (name "Net-(U13T-A1)") (class "Default")
      (node (ref "R35T") (pin "1") (pinfunction "1_1") (pintype "passive"))
      (node (ref "U13T") (pin "8") (pinfunction "A1_8") (pintype "input"))
    )
    (net (code "96") (name "Net-(U18T-~{FLT})") (class "Default")
      (node (ref "R58T") (pin "1") (pinfunction "1_1") (pintype "passive"))
      (node (ref "U18T") (pin "8") (pinfunction "~{FLT}_8") (pintype "open_collector"))
    )
    (net (code "97") (name "Net-(U19T-~{FLT})") (class "Default")
      (node (ref "R59T") (pin "1") (pinfunction "1_1") (pintype "passive"))
      (node (ref "U19T") (pin "8") (pinfunction "~{FLT}_8") (pintype "open_collector"))
    )
    (net (code "98") (name "P3.3VA") (class "Default")
      (node (ref "C11T") (pin "1") (pinfunction "1_1") (pintype "passive"))
      (node (ref "C12T") (pin "1") (pinfunction "1_1") (pintype "passive"))
      (node (ref "C19T") (pin "1") (pinfunction "1_1") (pintype "passive"))
      (node (ref "C20T") (pin "1") (pinfunction "1_1") (pintype "passive"))
      (node (ref "C28T") (pin "1") (pinfunction "1_1") (pintype "passive"))
      (node (ref "C29T") (pin "1") (pinfunction "1_1") (pintype "passive"))
      (node (ref "C35T") (pin "1") (pinfunction "1_1") (pintype "passive"))
      (node (ref "D10T") (pin "1") (pinfunction "K_1") (pintype "passive"))
      (node (ref "D11T") (pin "1") (pinfunction "K_1") (pintype "passive"))
      (node (ref "D12T") (pin "1") (pinfunction "K_1") (pintype "passive"))
      (node (ref "D13T") (pin "1") (pinfunction "K_1") (pintype "passive"))
      (node (ref "D14T") (pin "1") (pinfunction "K_1") (pintype "passive"))
      (node (ref "D15T") (pin "1") (pinfunction "K_1") (pintype "passive"))
      (node (ref "D16T") (pin "1") (pinfunction "K_1") (pintype "passive"))
      (node (ref "D17T") (pin "1") (pinfunction "K_1") (pintype "passive"))
      (node (ref "D18T") (pin "1") (pinfunction "K_1") (pintype "passive"))
      (node (ref "D19T") (pin "1") (pinfunction "K_1") (pintype "passive"))
      (node (ref "R16T") (pin "2") (pinfunction "2_2") (pintype "passive"))
      (node (ref "R31T") (pin "2") (pinfunction "2_2") (pintype "passive"))
      (node (ref "R32T") (pin "2") (pinfunction "2_2") (pintype "passive"))
      (node (ref "R35T") (pin "2") (pinfunction "2_2") (pintype "passive"))
      (node (ref "R37T") (pin "2") (pinfunction "2_2") (pintype "passive"))
      (node (ref "R58T") (pin "2") (pinfunction "2_2") (pintype "passive"))
      (node (ref "U11T") (pin "5") (pinfunction "V+_5") (pintype "power_in"))
      (node (ref "U13T") (pin "5") (pinfunction "V+_5") (pintype "power_in"))
      (node (ref "U14T") (pin "5") (pinfunction "V+_5") (pintype "power_in"))
      (node (ref "U16T") (pin "5") (pinfunction "V+_5") (pintype "power_in"))
      (node (ref "U18T") (pin "1") (pinfunction "OUT_1") (pintype "power_in"))
      (node (ref "U18T") (pin "4") (pinfunction "OUT_4") (pintype "power_in"))
    )
    (net (code "99") (name "P3.3VD") (class "Default")
      (node (ref "C17T") (pin "1") (pinfunction "1_1") (pintype "passive"))
      (node (ref "C26T") (pin "1") (pinfunction "1_1") (pintype "passive"))
      (node (ref "C36T") (pin "1") (pinfunction "1_1") (pintype "passive"))
      (node (ref "JDUT") (pin "A1") (pinfunction "A1_A1") (pintype "passive"))
      (node (ref "JPI") (pin "A1") (pinfunction "A1_A1") (pintype "passive"))
      (node (ref "P20T") (pin "2") (pinfunction "2_2") (pintype "passive"))
      (node (ref "P21T") (pin "1") (pinfunction "1_1") (pintype "passive"))
      (node (ref "R59T") (pin "2") (pinfunction "2_2") (pintype "passive"))
      (node (ref "U12T") (pin "1") (pinfunction "VCCA_1") (pintype "power_in"))
      (node (ref "U12T") (pin "2") (pinfunction "DIR_2") (pintype "input"))
      (node (ref "U15T") (pin "1") (pinfunction "VCCA_1") (pintype "power_in"))
      (node (ref "U19T") (pin "1") (pinfunction "OUT_1") (pintype "power_in"))
      (node (ref "U19T") (pin "4") (pinfunction "OUT_4") (pintype "power_in"))
    )
    (net (code "100") (name "P3.3V_DUT") (class "Default")
      (node (ref "C14T") (pin "1") (pinfunction "1_1") (pintype "passive"))
      (node (ref "C18T") (pin "1") (pinfunction "1_1") (pintype "passive"))
      (node (ref "C27T") (pin "1") (pinfunction "1_1") (pintype "passive"))
      (node (ref "C30T") (pin "1") (pinfunction "1_1") (pintype "passive"))
      (node (ref "R22T") (pin "1") (pinfunction "1_1") (pintype "passive"))
      (node (ref "U10T") (pin "2") (pinfunction "OUT_2") (pintype "power_in"))
      (node (ref "U10T") (pin "4") (pinfunction "TAB_4") (pintype "power_in"))
      (node (ref "U12T") (pin "23") (pinfunction "VCCB_23") (pintype "power_in"))
      (node (ref "U12T") (pin "24") (pinfunction "VCCB_24") (pintype "power_in"))
      (node (ref "U15T") (pin "23") (pinfunction "VCCB_23") (pintype "power_in"))
      (node (ref "U15T") (pin "24") (pinfunction "VCCB_24") (pintype "power_in"))
      (node (ref "U17T") (pin "6") (pinfunction "VDD_6") (pintype "power_in"))
    )
    (net (code "101") (name "P5.0V") (class "Default")
      (node (ref "C33T") (pin "1") (pinfunction "1_1") (pintype "passive"))
      (node (ref "C34T") (pin "1") (pinfunction "1_1") (pintype "passive"))
      (node (ref "C39T") (pin "1") (pinfunction "1_1") (pintype "passive"))
      (node (ref "C46T") (pin "1") (pinfunction "1_1") (pintype "passive"))
      (node (ref "C47T") (pin "1") (pinfunction "1_1") (pintype "passive"))
      (node (ref "D20T") (pin "1") (pinfunction "A_1") (pintype "passive"))
      (node (ref "L10T") (pin "2") (pinfunction "2_2") (pintype "passive"))
      (node (ref "P18T") (pin "1") (pinfunction "1_1") (pintype "passive"))
      (node (ref "P18T") (pin "3") (pinfunction "3_3") (pintype "passive"))
      (node (ref "R62T") (pin "2") (pinfunction "2_2") (pintype "passive"))
      (node (ref "U18T") (pin "2") (pinfunction "IN_2") (pintype "power_in"))
      (node (ref "U18T") (pin "7") (pinfunction "~{SD}_7") (pintype "input"))
      (node (ref "U19T") (pin "2") (pinfunction "IN_2") (pintype "power_in"))
      (node (ref "U19T") (pin "7") (pinfunction "~{SD}_7") (pintype "input"))
    )
    (net (code "102") (name "P12V") (class "Default")
      (node (ref "C21T") (pin "2") (pinfunction "2_2") (pintype "passive"))
      (node (ref "C40T") (pin "1") (pinfunction "1_1") (pintype "passive"))
      (node (ref "C41T") (pin "2") (pinfunction "2_2") (pintype "passive"))
      (node (ref "C42T") (pin "2") (pinfunction "2_2") (pintype "passive"))
      (node (ref "C43T") (pin "1") (pinfunction "1_1") (pintype "passive"))
      (node (ref "C44T") (pin "1") (pinfunction "1_1") (pintype "passive"))
      (node (ref "D21T") (pin "1") (pinfunction "A_1") (pintype "passive"))
      (node (ref "JP10T") (pin "1") (pintype "power_in"))
      (node (ref "Q10T") (pin "4") (pinfunction "S_4") (pintype "passive"))
      (node (ref "R36T") (pin "2") (pinfunction "2_2") (pintype "passive"))
      (node (ref "U20T") (pin "1") (pinfunction "EN_1") (pintype "input"))
      (node (ref "U20T") (pin "8") (pinfunction "VIN_8") (pintype "power_in"))
    )
    (net (code "103") (name "unconnected-(JDUT-PadA19)") (class "Default")
      (node (ref "JDUT") (pin "A19") (pinfunction "A19_A19") (pintype "passive"))
    )
    (net (code "104") (name "unconnected-(JDUT-PadA32)") (class "Default")
      (node (ref "JDUT") (pin "A32") (pinfunction "A32_A32") (pintype "passive"))
    )
    (net (code "105") (name "unconnected-(JDUT-PadB17)") (class "Default")
      (node (ref "JDUT") (pin "B17") (pinfunction "B17_B17") (pintype "passive"))
    )
    (net (code "106") (name "unconnected-(JDUT-PadB30)") (class "Default")
      (node (ref "JDUT") (pin "B30") (pinfunction "B30_B30") (pintype "passive"))
    )
    (net (code "107") (name "unconnected-(JPI-PadA2)") (class "Default")
      (node (ref "JPI") (pin "A2") (pinfunction "A2_A2") (pintype "passive"))
    )
    (net (code "108") (name "unconnected-(JPI-PadA3)") (class "Default")
      (node (ref "JPI") (pin "A3") (pinfunction "A3_A3") (pintype "passive"))
    )
    (net (code "109") (name "unconnected-(JPI-PadA4)") (class "Default")
      (node (ref "JPI") (pin "A4") (pinfunction "A4_A4") (pintype "passive"))
    )
    (net (code "110") (name "unconnected-(JPI-PadA5)") (class "Default")
      (node (ref "JPI") (pin "A5") (pinfunction "A5_A5") (pintype "passive"))
    )
    (net (code "111") (name "unconnected-(JPI-PadA6)") (class "Default")
      (node (ref "JPI") (pin "A6") (pinfunction "A6_A6") (pintype "passive"))
    )
    (net (code "112") (name "unconnected-(JPI-PadA7)") (class "Default")
      (node (ref "JPI") (pin "A7") (pinfunction "A7_A7") (pintype "passive"))
    )
    (net (code "113") (name "unconnected-(JPI-PadA8)") (class "Default")
      (node (ref "JPI") (pin "A8") (pinfunction "A8_A8") (pintype "passive"))
    )
    (net (code "114") (name "unconnected-(JPI-PadA9)") (class "Default")
      (node (ref "JPI") (pin "A9") (pinfunction "A9_A9") (pintype "passive"))
    )
    (net (code "115") (name "unconnected-(JPI-PadA10)") (class "Default")
      (node (ref "JPI") (pin "A10") (pinfunction "A10_A10") (pintype "passive"))
    )
    (net (code "116") (name "unconnected-(JPI-PadA11)") (class "Default")
      (node (ref "JPI") (pin "A11") (pinfunction "A11_A11") (pintype "passive"))
    )
    (net (code "117") (name "unconnected-(JPI-PadA13)") (class "Default")
      (node (ref "JPI") (pin "A13") (pinfunction "A13_A13") (pintype "passive"))
    )
    (net (code "118") (name "unconnected-(JPI-PadA16)") (class "Default")
      (node (ref "JPI") (pin "A16") (pinfunction "A16_A16") (pintype "passive"))
    )
    (net (code "119") (name "unconnected-(JPI-PadA17)") (class "Default")
      (node (ref "JPI") (pin "A17") (pinfunction "A17_A17") (pintype "passive"))
    )
    (net (code "120") (name "unconnected-(JPI-PadA19)") (class "Default")
      (node (ref "JPI") (pin "A19") (pinfunction "A19_A19") (pintype "passive"))
    )
    (net (code "121") (name "unconnected-(JPI-PadA21)") (class "Default")
      (node (ref "JPI") (pin "A21") (pinfunction "A21_A21") (pintype "passive"))
    )
    (net (code "122") (name "unconnected-(JPI-PadA22)") (class "Default")
      (node (ref "JPI") (pin "A22") (pinfunction "A22_A22") (pintype "passive"))
    )
    (net (code "123") (name "unconnected-(JPI-PadB1)") (class "Default")
      (node (ref "JPI") (pin "B1") (pinfunction "B1_B1") (pintype "passive"))
    )
    (net (code "124") (name "unconnected-(JPI-PadB2)") (class "Default")
      (node (ref "JPI") (pin "B2") (pinfunction "B2_B2") (pintype "passive"))
    )
    (net (code "125") (name "unconnected-(JPI-PadB3)") (class "Default")
      (node (ref "JPI") (pin "B3") (pinfunction "B3_B3") (pintype "passive"))
    )
    (net (code "126") (name "unconnected-(JPI-PadB5)") (class "Default")
      (node (ref "JPI") (pin "B5") (pinfunction "B5_B5") (pintype "passive"))
    )
    (net (code "127") (name "unconnected-(JPI-PadB6)") (class "Default")
      (node (ref "JPI") (pin "B6") (pinfunction "B6_B6") (pintype "passive"))
    )
    (net (code "128") (name "unconnected-(JPI-PadB8)") (class "Default")
      (node (ref "JPI") (pin "B8") (pinfunction "B8_B8") (pintype "passive"))
    )
    (net (code "129") (name "unconnected-(JPI-PadB9)") (class "Default")
      (node (ref "JPI") (pin "B9") (pinfunction "B9_B9") (pintype "passive"))
    )
    (net (code "130") (name "unconnected-(JPI-PadB10)") (class "Default")
      (node (ref "JPI") (pin "B10") (pinfunction "B10_B10") (pintype "passive"))
    )
    (net (code "131") (name "unconnected-(JPI-PadB11)") (class "Default")
      (node (ref "JPI") (pin "B11") (pinfunction "B11_B11") (pintype "passive"))
    )
    (net (code "132") (name "unconnected-(JPI-PadB12)") (class "Default")
      (node (ref "JPI") (pin "B12") (pinfunction "B12_B12") (pintype "passive"))
    )
    (net (code "133") (name "unconnected-(JPI-PadB17)") (class "Default")
      (node (ref "JPI") (pin "B17") (pinfunction "B17_B17") (pintype "passive"))
    )
    (net (code "134") (name "unconnected-(JPI-PadB20)") (class "Default")
      (node (ref "JPI") (pin "B20") (pinfunction "B20_B20") (pintype "passive"))
    )
    (net (code "135") (name "unconnected-(JPI-PadB23)") (class "Default")
      (node (ref "JPI") (pin "B23") (pinfunction "B23_B23") (pintype "passive"))
    )
    (net (code "136") (name "unconnected-(JPI-PadB24)") (class "Default")
      (node (ref "JPI") (pin "B24") (pinfunction "B24_B24") (pintype "passive"))
    )
    (net (code "137") (name "unconnected-(JPI-PadB27)") (class "Default")
      (node (ref "JPI") (pin "B27") (pinfunction "B27_B27") (pintype "passive"))
    )
    (net (code "138") (name "unconnected-(JPI-PadB28)") (class "Default")
      (node (ref "JPI") (pin "B28") (pinfunction "B28_B28") (pintype "passive"))
    )
    (net (code "139") (name "unconnected-(JPI-PadB30)") (class "Default")
      (node (ref "JPI") (pin "B30") (pinfunction "B30_B30") (pintype "passive"))
    )
    (net (code "140") (name "unconnected-(P17T-Pad2)") (class "Default")
      (node (ref "P17T") (pin "2") (pinfunction "2_2") (pintype "passive"))
    )
    (net (code "141") (name "unconnected-(P17T-Pad4)") (class "Default")
      (node (ref "P17T") (pin "4") (pinfunction "4_4") (pintype "passive"))
    )
    (net (code "142") (name "unconnected-(P17T-Pad11)") (class "Default")
      (node (ref "P17T") (pin "11") (pinfunction "11_11") (pintype "passive"))
    )
    (net (code "143") (name "unconnected-(P17T-Pad14)") (class "Default")
      (node (ref "P17T") (pin "14") (pinfunction "14_14") (pintype "passive"))
    )
    (net (code "144") (name "unconnected-(P17T-Pad16)") (class "Default")
      (node (ref "P17T") (pin "16") (pinfunction "16_16") (pintype "passive"))
    )
    (net (code "145") (name "unconnected-(P17T-Pad17)") (class "Default")
      (node (ref "P17T") (pin "17") (pinfunction "17_17") (pintype "passive"))
    )
    (net (code "146") (name "unconnected-(P17T-Pad19)") (class "Default")
      (node (ref "P17T") (pin "19") (pinfunction "19_19") (pintype "passive"))
    )
    (net (code "147") (name "unconnected-(P18T-Pad2)") (class "Default")
      (node (ref "P18T") (pin "2") (pinfunction "2_2") (pintype "passive"))
    )
    (net (code "148") (name "unconnected-(P18T-Pad18)") (class "Default")
      (node (ref "P18T") (pin "18") (pinfunction "18_18") (pintype "passive"))
    )
    (net (code "149") (name "unconnected-(P18T-Pad20)") (class "Default")
      (node (ref "P18T") (pin "20") (pinfunction "20_20") (pintype "passive"))
    )
    (net (code "150") (name "unconnected-(U11T-VREF-Pad1)") (class "Default")
      (node (ref "U11T") (pin "1") (pinfunction "VREF_1") (pintype "power_in+no_connect"))
    )
    (net (code "151") (name "unconnected-(U12T-B6-Pad16)") (class "Default")
      (node (ref "U12T") (pin "16") (pinfunction "B6_16") (pintype "input"))
    )
    (net (code "152") (name "unconnected-(U12T-B7-Pad15)") (class "Default")
      (node (ref "U12T") (pin "15") (pinfunction "B7_15") (pintype "input"))
    )
    (net (code "153") (name "unconnected-(U12T-B8-Pad14)") (class "Default")
      (node (ref "U12T") (pin "14") (pinfunction "B8_14") (pintype "input"))
    )
    (net (code "154") (name "unconnected-(U13T-IN2-Pad14)") (class "Default")
      (node (ref "U13T") (pin "14") (pinfunction "IN2_14") (pintype "input"))
    )
    (net (code "155") (name "unconnected-(U13T-IN3-Pad13)") (class "Default")
      (node (ref "U13T") (pin "13") (pinfunction "IN3_13") (pintype "input"))
    )
    (net (code "156") (name "unconnected-(U13T-IN4-Pad12)") (class "Default")
      (node (ref "U13T") (pin "12") (pinfunction "IN4_12") (pintype "input"))
    )
    (net (code "157") (name "unconnected-(U13T-IN5-Pad11)") (class "Default")
      (node (ref "U13T") (pin "11") (pinfunction "IN5_11") (pintype "input"))
    )
    (net (code "158") (name "unconnected-(U13T-IN6-Pad10)") (class "Default")
      (node (ref "U13T") (pin "10") (pinfunction "IN6_10") (pintype "input"))
    )
    (net (code "159") (name "unconnected-(U13T-VREF-Pad1)") (class "Default")
      (node (ref "U13T") (pin "1") (pinfunction "VREF_1") (pintype "power_in+no_connect"))
    )
    (net (code "160") (name "unconnected-(U15T-A5-Pad7)") (class "Default")
      (node (ref "U15T") (pin "7") (pinfunction "A5_7") (pintype "bidirectional"))
    )
    (net (code "161") (name "unconnected-(U15T-A6-Pad8)") (class "Default")
      (node (ref "U15T") (pin "8") (pinfunction "A6_8") (pintype "bidirectional"))
    )
    (net (code "162") (name "unconnected-(U15T-A7-Pad9)") (class "Default")
      (node (ref "U15T") (pin "9") (pinfunction "A7_9") (pintype "bidirectional"))
    )
    (net (code "163") (name "unconnected-(U15T-A8-Pad10)") (class "Default")
      (node (ref "U15T") (pin "10") (pinfunction "A8_10") (pintype "bidirectional"))
    )
    (net (code "164") (name "unconnected-(U17T-TRI-Pad1)") (class "Default")
      (node (ref "U17T") (pin "1") (pinfunction "TRI_1") (pintype "input+no_connect"))
    )
    (net (code "165") (name "unconnected-(U18T-NC-Pad5)") (class "Default")
      (node (ref "U18T") (pin "5") (pinfunction "NC_5") (pintype "passive"))
    )
    (net (code "166") (name "unconnected-(U19T-NC-Pad5)") (class "Default")
      (node (ref "U19T") (pin "5") (pinfunction "NC_5") (pintype "passive"))
    )
  )
)
